# PX4FMUv1_7.net
KiCad netlist of a schematic drawn in EAGLE
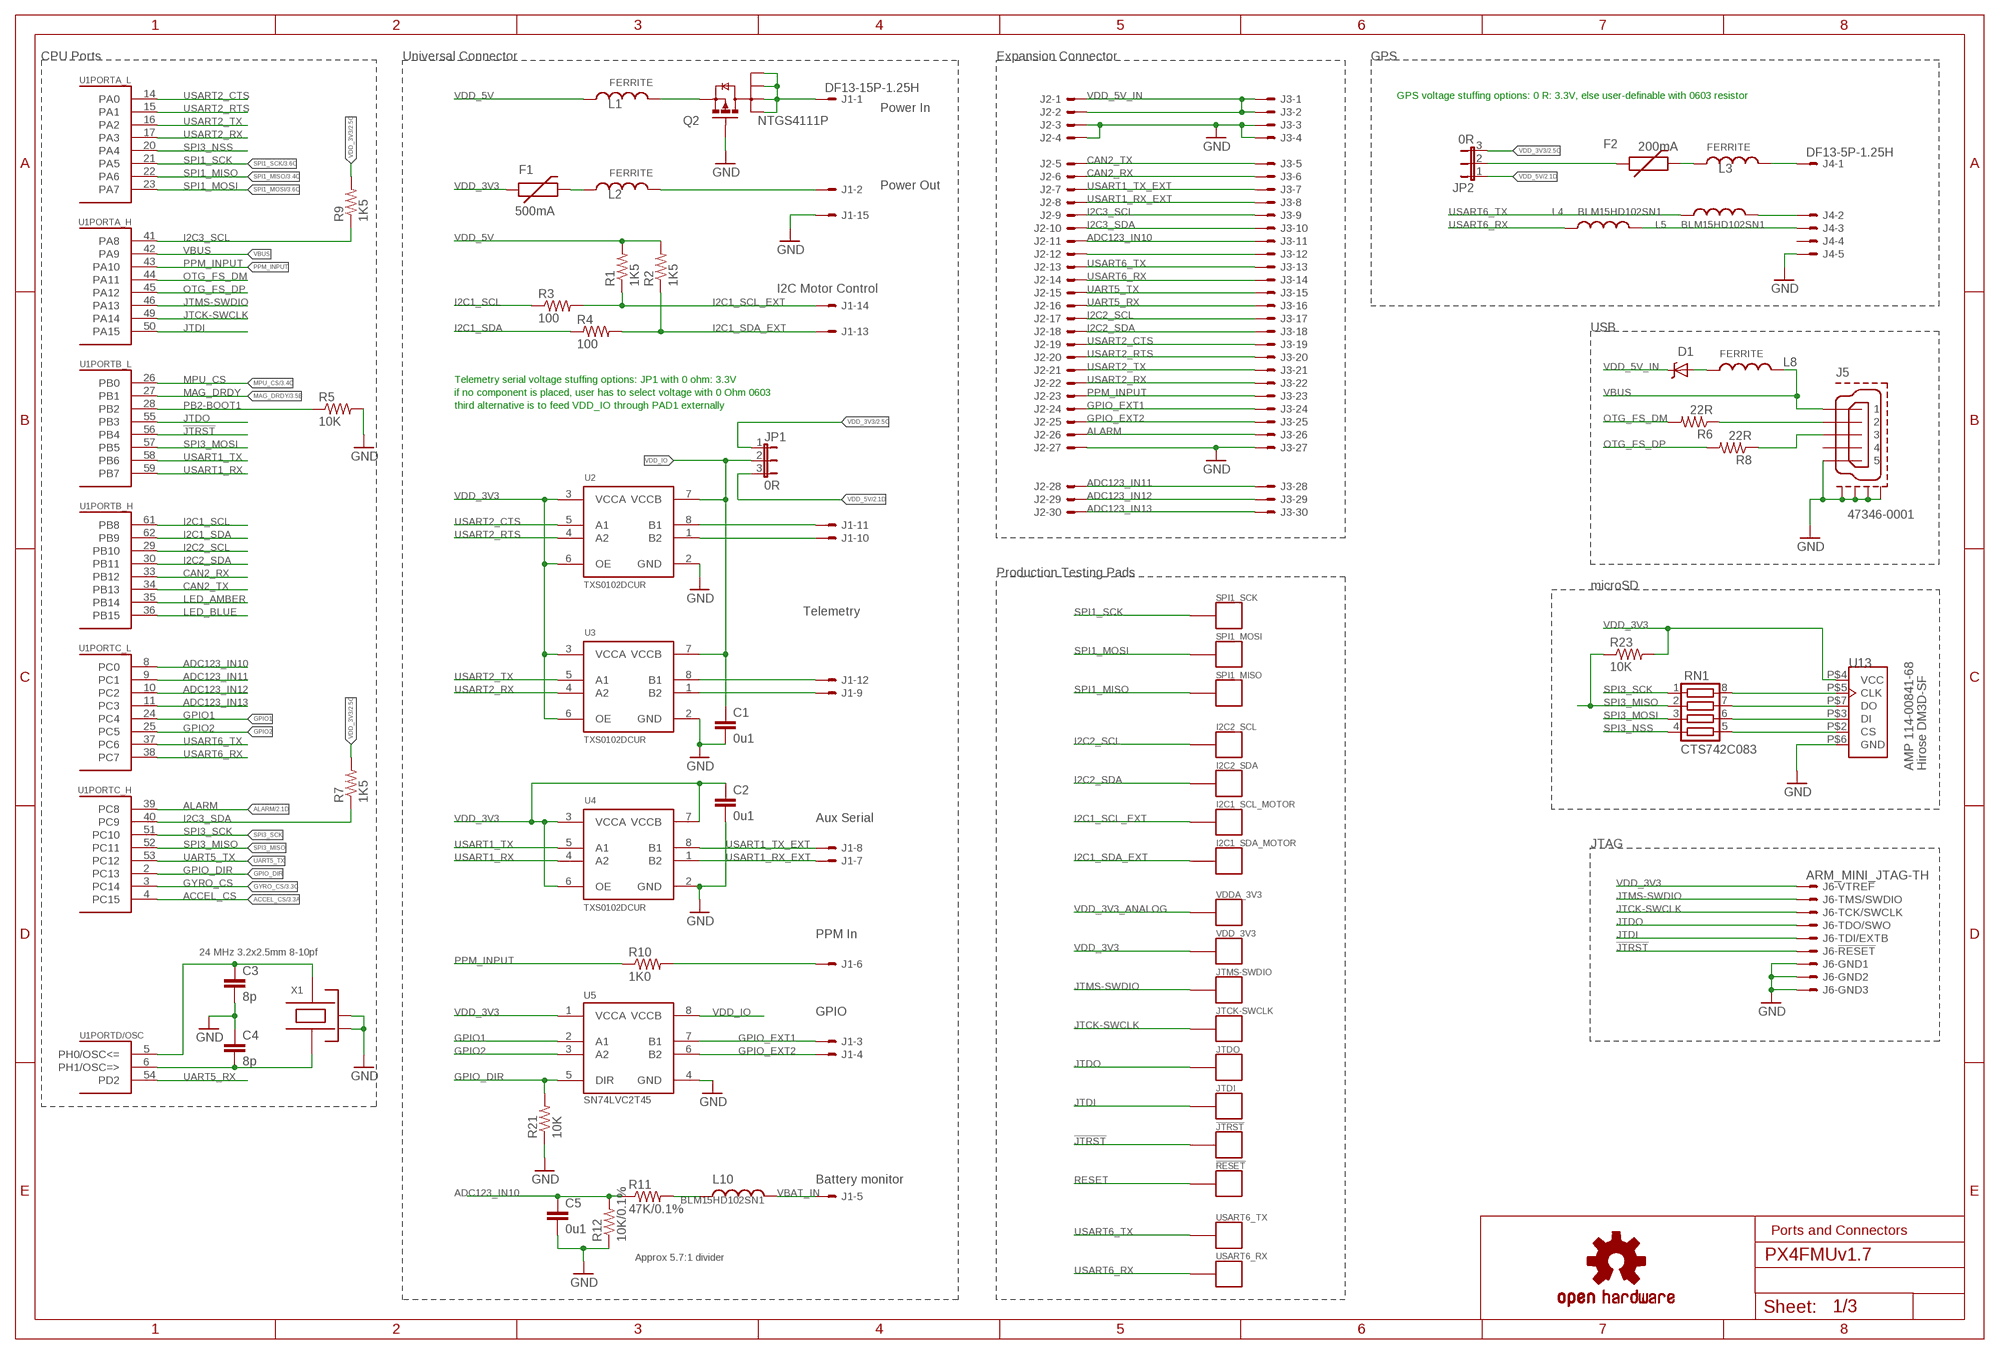
[diagram p0: schematic, sheet 1]
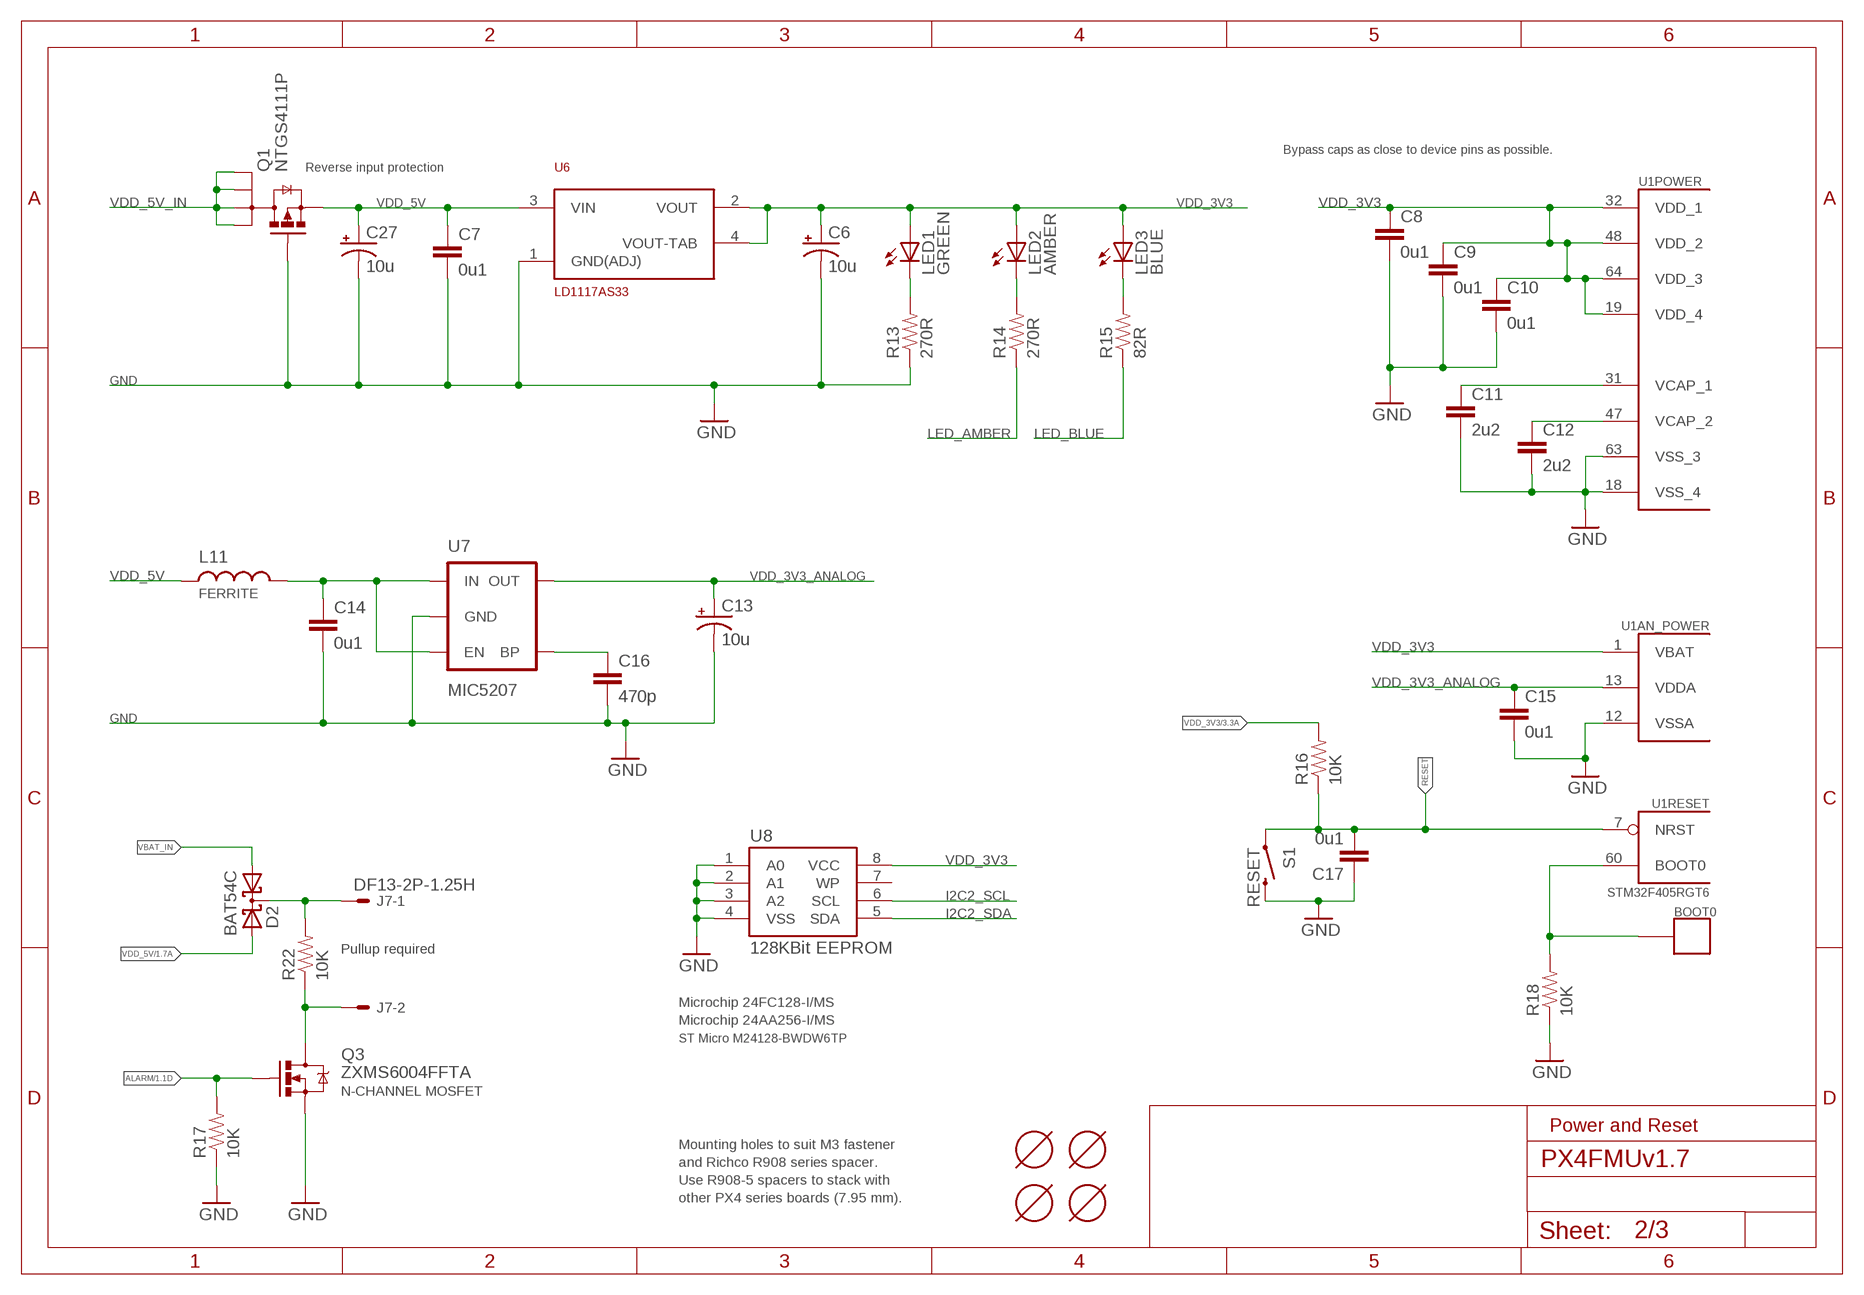
[diagram p1: schematic, sheet 2]
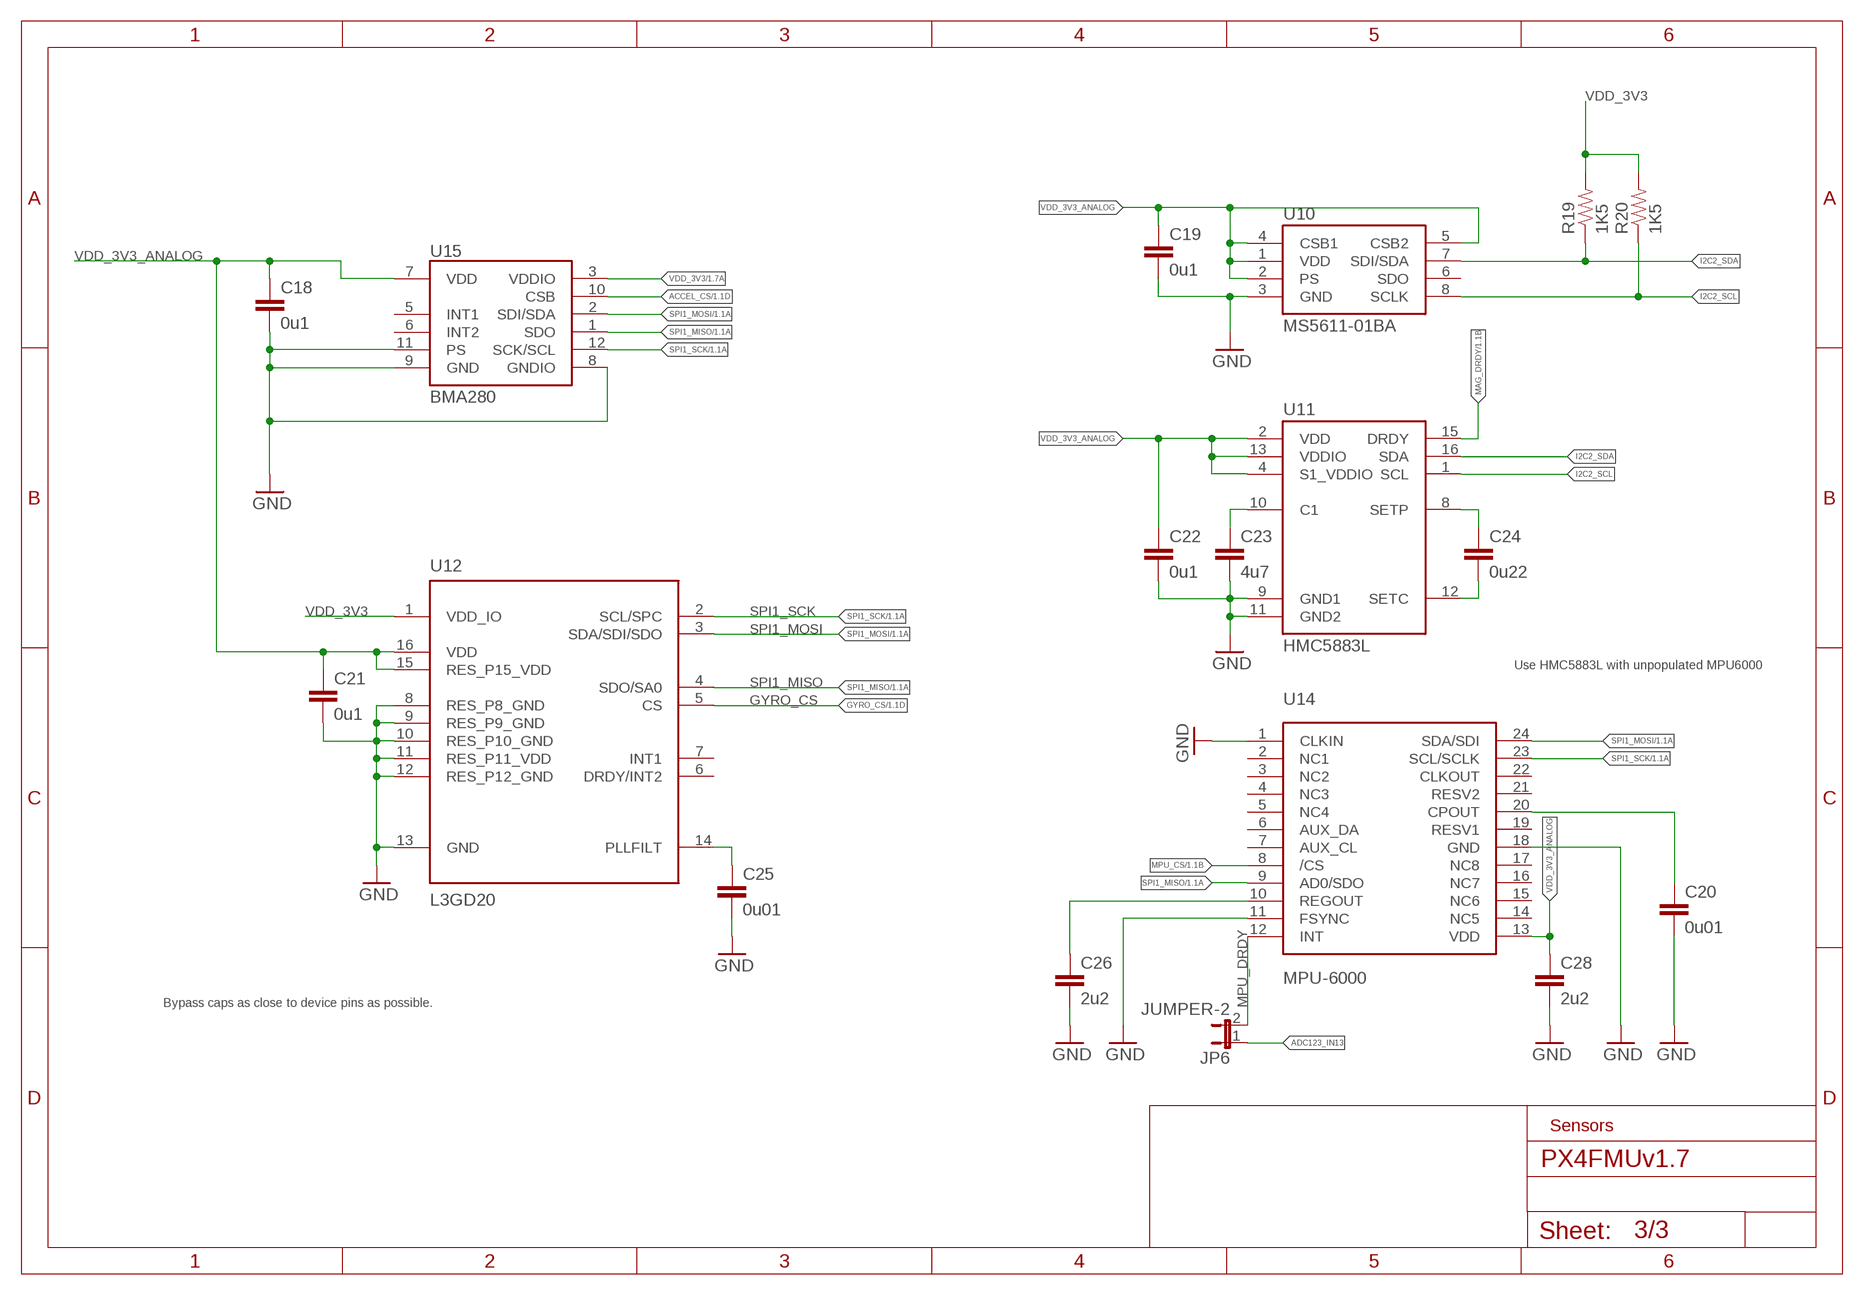
[diagram p2: schematic, sheet 3]

(export (version "E")
  (design (tool "Eeschema 10.0.6"))
  (components
    (comp (ref "BOOT0")
      (value "PAD.04")
      (footprint "eagle-import:PAD.04X.04")
      (libsource (lib "eagle-import") (part "PAD.04"))
    )
    (comp (ref "C6")
      (value "10u")
      (footprint "eagle-import:EIA3216")
      (fields (field (name "PARTNO") "F931A106MAA"))
      (libsource (lib "eagle-import") (part "CAP_POL1206"))
    )
    (comp (ref "C7")
      (value "0u1")
      (footprint "eagle-import:0402-CAP")
      (fields (field (name "PARTNO") "CC0402ZRY5V7BB104"))
      (libsource (lib "eagle-import") (part "CAP0402-CAP"))
    )
    (comp (ref "C8")
      (value "0u1")
      (footprint "eagle-import:0402-CAP")
      (fields (field (name "PARTNO") "CC0402ZRY5V7BB104"))
      (libsource (lib "eagle-import") (part "CAP0402-CAP"))
    )
    (comp (ref "C9")
      (value "0u1")
      (footprint "eagle-import:0402-CAP")
      (fields (field (name "PARTNO") "CC0402ZRY5V7BB104"))
      (libsource (lib "eagle-import") (part "CAP0402-CAP"))
    )
    (comp (ref "C10")
      (value "0u1")
      (footprint "eagle-import:0402-CAP")
      (fields (field (name "PARTNO") "CC0402ZRY5V7BB104"))
      (libsource (lib "eagle-import") (part "CAP0402-CAP"))
    )
    (comp (ref "C11")
      (value "2u2")
      (footprint "eagle-import:0402-CAP")
      (fields (field (name "PARTNO") "C1608Y5V1C225Z"))
      (libsource (lib "eagle-import") (part "CAP0402-CAP"))
    )
    (comp (ref "C12")
      (value "2u2")
      (footprint "eagle-import:0402-CAP")
      (fields (field (name "PARTNO") "C1608Y5V1C225Z"))
      (libsource (lib "eagle-import") (part "CAP0402-CAP"))
    )
    (comp (ref "C13")
      (value "10u")
      (footprint "eagle-import:EIA3216")
      (fields (field (name "PARTNO") "F931A106MAA"))
      (libsource (lib "eagle-import") (part "CAP_POL1206"))
    )
    (comp (ref "C14")
      (value "0u1")
      (footprint "eagle-import:0402-CAP")
      (fields (field (name "PARTNO") "CC0402ZRY5V7BB104"))
      (libsource (lib "eagle-import") (part "CAP0402-CAP"))
    )
    (comp (ref "C15")
      (value "0u1")
      (footprint "eagle-import:0402-CAP")
      (fields (field (name "PARTNO") "CC0402ZRY5V7BB104"))
      (libsource (lib "eagle-import") (part "CAP0402-CAP"))
    )
    (comp (ref "C16")
      (value "470p")
      (footprint "eagle-import:0402-CAP")
      (fields (field (name "PARTNO") "CC0402KRX7R9BB471"))
      (libsource (lib "eagle-import") (part "CAP0402-CAP"))
    )
    (comp (ref "C17")
      (value "0u1")
      (footprint "eagle-import:0402-CAP")
      (fields (field (name "PARTNO") "CC0402ZRY5V7BB104"))
      (libsource (lib "eagle-import") (part "CAP0402-CAP"))
    )
    (comp (ref "C27")
      (value "10u")
      (footprint "eagle-import:EIA3216")
      (fields (field (name "PARTNO") "F931A106MAA"))
      (libsource (lib "eagle-import") (part "CAP_POL1206"))
    )
    (comp (ref "D2")
      (value "BAT54C")
      (footprint "eagle-import:SOT23-3")
      (fields (field (name "PARTNO") "BAT54C-7-F"))
      (libsource (lib "eagle-import") (part "BAT54C"))
    )
    (comp (ref "J7")
      (value "DF13-2P-1.25H")
      (footprint "eagle-import:DF13A-2P-1.25H")
      (fields (field (name "PARTNO") "DF13-2P-1.25H(20)"))
      (libsource (lib "eagle-import") (part "DF13-2P-1.25?H"))
    )
    (comp (ref "L11")
      (value "FERRITE")
      (footprint "eagle-import:0402-IND")
      (fields (field (name "PARTNO") "BKP1005HS121-T"))
      (libsource (lib "eagle-import") (part "INDUCTOR0402"))
    )
    (comp (ref "LED1")
      (value "GREEN")
      (footprint "eagle-import:LED-0603")
      (fields (field (name "PARTNO") "LNJ337W83RA"))
      (libsource (lib "eagle-import") (part "LED0603"))
    )
    (comp (ref "LED2")
      (value "AMBER")
      (footprint "eagle-import:LED-0603")
      (fields (field (name "PARTNO") "LNJ437W84RA"))
      (libsource (lib "eagle-import") (part "LED0603"))
    )
    (comp (ref "LED3")
      (value "BLUE")
      (footprint "eagle-import:LED-0603")
      (fields (field (name "PARTNO") "LNJ937W8CRA"))
      (libsource (lib "eagle-import") (part "LED0603"))
    )
    (comp (ref "Q1")
      (value "NTGS4111P")
      (footprint "eagle-import:TSOP-6")
      (libsource (lib "eagle-import") (part "NTGS4111P"))
    )
    (comp (ref "Q3")
      (value "ZXMS6004FFTA")
      (footprint "eagle-import:SOT23-3")
      (libsource (lib "eagle-import") (part "MOSFET-NCHANNELSMD"))
    )
    (comp (ref "R13")
      (value "270R")
      (footprint "eagle-import:0402-RES")
      (fields (field (name "PARTNO") "RC0402JR-07270RL"))
      (libsource (lib "eagle-import") (part "RESISTOR0402-RES"))
    )
    (comp (ref "R14")
      (value "270R")
      (footprint "eagle-import:0402-RES")
      (fields (field (name "PARTNO") "RC0402JR-07270RL"))
      (libsource (lib "eagle-import") (part "RESISTOR0402-RES"))
    )
    (comp (ref "R15")
      (value "82R")
      (footprint "eagle-import:0402-RES")
      (fields (field (name "PARTNO") "RC0402JR-0782RL"))
      (libsource (lib "eagle-import") (part "RESISTOR0402-RES"))
    )
    (comp (ref "R16")
      (value "10K")
      (footprint "eagle-import:0402-RES")
      (fields (field (name "PARTNO") "RMCF0402FT10K0"))
      (libsource (lib "eagle-import") (part "RESISTOR0402-RES"))
    )
    (comp (ref "R17")
      (value "10K")
      (footprint "eagle-import:0402-RES")
      (fields (field (name "PARTNO") "RMCF0402FT10K0"))
      (libsource (lib "eagle-import") (part "RESISTOR0402-RES"))
    )
    (comp (ref "R18")
      (value "10K")
      (footprint "eagle-import:0402-RES")
      (fields (field (name "PARTNO") "RMCF0402FT10K0"))
      (libsource (lib "eagle-import") (part "RESISTOR0402-RES"))
    )
    (comp (ref "R22")
      (value "10K")
      (footprint "eagle-import:0402-RES")
      (fields (field (name "PARTNO") "RMCF0402FT10K0"))
      (libsource (lib "eagle-import") (part "RESISTOR0402-RES"))
    )
    (comp (ref "S1")
      (value "RESET")
      (footprint "eagle-import:EVQP7J01K")
      (fields (field (name "PARTNO") "EVQP7J01K"))
      (libsource (lib "eagle-import") (part "SWITCH-MOMENTARY-2"))
    )
    (comp (ref "U$1")
      (value "MOUNT-HOLE3.1MM")
      (footprint "eagle-import:MOUNT-HOLE3.1")
      (libsource (lib "eagle-import") (part "MOUNT-HOLE3.1MM"))
    )
    (comp (ref "U$2")
      (value "MOUNT-HOLE3.1MM")
      (footprint "eagle-import:MOUNT-HOLE3.1")
      (libsource (lib "eagle-import") (part "MOUNT-HOLE3.1MM"))
    )
    (comp (ref "U$3")
      (value "MOUNT-HOLE3.1MM")
      (footprint "eagle-import:MOUNT-HOLE3.1")
      (libsource (lib "eagle-import") (part "MOUNT-HOLE3.1MM"))
    )
    (comp (ref "U$4")
      (value "MOUNT-HOLE3.1MM")
      (footprint "eagle-import:MOUNT-HOLE3.1")
      (libsource (lib "eagle-import") (part "MOUNT-HOLE3.1MM"))
    )
    (comp (ref "U1")
      (value "STM32F405RGT6")
      (footprint "eagle-import:TQFP64")
      (fields (field (name "PARTNO") "STM32F405RGT6"))
      (libsource (lib "eagle-import") (part "STM32F20X_TQFP64"))
    )
    (comp (ref "U6")
      (value "LD1117AS33")
      (footprint "eagle-import:SOT-223")
      (libsource (lib "eagle-import") (part "LD1117AS33"))
    )
    (comp (ref "U7")
      (value "MIC5207")
      (footprint "eagle-import:SOT23-5")
      (fields (field (name "PARTNO") "MIC5207-3.3YM5"))
      (libsource (lib "eagle-import") (part "V_REG_LDOSMD"))
    )
    (comp (ref "U8")
      (value "128KBit EEPROM")
      (footprint "eagle-import:MSOP-8")
      (fields (field (name "PARTNO") "24FC128-I/MS"))
      (libsource (lib "eagle-import") (part "EEPROM-I2CMSOP"))
    )
    (comp (ref "!JTRST")
      (value "PAD.04")
      (footprint "eagle-import:PAD.04X.04")
      (libsource (lib "eagle-import") (part "PAD.04"))
    )
    (comp (ref "!RESET")
      (value "PAD.04")
      (footprint "eagle-import:PAD.04X.04")
      (libsource (lib "eagle-import") (part "PAD.04"))
    )
    (comp (ref "C1")
      (value "0u1")
      (footprint "eagle-import:0402-CAP")
      (fields (field (name "PARTNO") "CC0402ZRY5V7BB104"))
      (libsource (lib "eagle-import") (part "CAP0402-CAP"))
    )
    (comp (ref "C2")
      (value "0u1")
      (footprint "eagle-import:0402-CAP")
      (fields (field (name "PARTNO") "CC0402ZRY5V7BB104"))
      (libsource (lib "eagle-import") (part "CAP0402-CAP"))
    )
    (comp (ref "C3")
      (value "8p")
      (footprint "eagle-import:0402-CAP")
      (fields (field (name "PARTNO") "C1005C0G1H080C"))
      (libsource (lib "eagle-import") (part "CAP0402-CAP"))
    )
    (comp (ref "C4")
      (value "8p")
      (footprint "eagle-import:0402-CAP")
      (fields (field (name "PARTNO") "C1005C0G1H080C"))
      (libsource (lib "eagle-import") (part "CAP0402-CAP"))
    )
    (comp (ref "C5")
      (value "0u1")
      (footprint "eagle-import:0402-CAP")
      (fields (field (name "PARTNO") "CC0402ZRY5V7BB104"))
      (libsource (lib "eagle-import") (part "CAP0402-CAP"))
    )
    (comp (ref "D1")
      (value "MSS1P4-M3")
      (footprint "eagle-import:MICROSMP")
      (fields (field (name "PARTNO") "MSS1P4-M3/89A"))
      (libsource (lib "eagle-import") (part "DIODE-SCHOTTKY_MSMP"))
    )
    (comp (ref "F1")
      (value "500mA")
      (footprint "eagle-import:0402-PTC")
      (fields (field (name "PARTNO") "MF-FSMF050X-2"))
      (libsource (lib "eagle-import") (part "PTC0402"))
    )
    (comp (ref "F2")
      (value "200mA")
      (footprint "eagle-import:0402-PTC")
      (fields (field (name "PARTNO") "MF-FSMF020X-2"))
      (libsource (lib "eagle-import") (part "PTC0402"))
    )
    (comp (ref "I2C1_SCL_MOTOR")
      (value "PAD.03")
      (footprint "eagle-import:PAD.03X.03")
      (libsource (lib "eagle-import") (part "PAD.03"))
    )
    (comp (ref "I2C1_SDA_MOTOR")
      (value "PAD.03")
      (footprint "eagle-import:PAD.03X.03")
      (libsource (lib "eagle-import") (part "PAD.03"))
    )
    (comp (ref "I2C2_SCL")
      (value "PAD.03")
      (footprint "eagle-import:PAD.03X.03")
      (libsource (lib "eagle-import") (part "PAD.03"))
    )
    (comp (ref "I2C2_SDA")
      (value "PAD.04")
      (footprint "eagle-import:PAD.04X.04")
      (libsource (lib "eagle-import") (part "PAD.04"))
    )
    (comp (ref "J1")
      (value "DF13-15P-1.25H")
      (footprint "eagle-import:DF13A-15P-1.25H")
      (fields (field (name "PARTNO") "DF13A-15P-1.25H(20)"))
      (libsource (lib "eagle-import") (part "DF13-15P-1.25?H"))
    )
    (comp (ref "J2")
      (value "HEADER_2X15-REV")
      (footprint "eagle-import:HEADER_2MM_2X15_REVERSE")
      (fields (field (name "BOM") "EXCLUDE") (field (name "PARTNO") "953230-2000-AR-PR"))
      (libsource (lib "eagle-import") (part "HEADER_2X15-REV"))
    )
    (comp (ref "J3")
      (value "HEADER_2X15")
      (footprint "eagle-import:HEADER_2MM_2X15")
      (fields (field (name "PARTNO") "953230-2000-AR-PR"))
      (libsource (lib "eagle-import") (part "HEADER_2X15-SMD"))
    )
    (comp (ref "J4")
      (value "DF13-5P-1.25H")
      (footprint "eagle-import:DF13A-5P-1.25H")
      (fields (field (name "PARTNO") "DF13A-5P-1.25H(20)"))
      (libsource (lib "eagle-import") (part "DF13-5P-1.25?H"))
    )
    (comp (ref "J5")
      (value "47346-0001")
      (footprint "eagle-import:MOLEX-47346-0001")
      (libsource (lib "eagle-import") (part "MOLEX-47346-0001"))
    )
    (comp (ref "J6")
      (value "ARM_MINI_JTAG-TH")
      (footprint "eagle-import:FTSH-105-01-XXX-DV")
      (fields (field (name "PARTNO") "M50-3900542"))
      (libsource (lib "eagle-import") (part "ARM_MINI_JTAG-TH"))
    )
    (comp (ref "JP1")
      (value "0R")
      (footprint "eagle-import:SJ_3_0603_PASTE1&2")
      (fields (field (name "PARTNO") "RMCF0402ZT0R00"))
      (libsource (lib "eagle-import") (part "JUMPER-30603"))
    )
    (comp (ref "JP2")
      (value "0R")
      (footprint "eagle-import:SJ_3_0603_PASTE1&2")
      (fields (field (name "PARTNO") "RMCF0402ZT0R00"))
      (libsource (lib "eagle-import") (part "JUMPER-30603"))
    )
    (comp (ref "JTCK-SWCLK")
      (value "PAD.04")
      (footprint "eagle-import:PAD.04X.04")
      (libsource (lib "eagle-import") (part "PAD.04"))
    )
    (comp (ref "JTDI")
      (value "PAD.04")
      (footprint "eagle-import:PAD.04X.04")
      (libsource (lib "eagle-import") (part "PAD.04"))
    )
    (comp (ref "JTDO")
      (value "PAD.04")
      (footprint "eagle-import:PAD.04X.04")
      (libsource (lib "eagle-import") (part "PAD.04"))
    )
    (comp (ref "JTMS-SWDIO")
      (value "PAD.04")
      (footprint "eagle-import:PAD.04X.04")
      (libsource (lib "eagle-import") (part "PAD.04"))
    )
    (comp (ref "L1")
      (value "FERRITE")
      (footprint "eagle-import:0402-IND")
      (fields (field (name "PARTNO") "BKP1005HS121-T"))
      (libsource (lib "eagle-import") (part "INDUCTOR0402"))
    )
    (comp (ref "L2")
      (value "FERRITE")
      (footprint "eagle-import:0402-IND")
      (fields (field (name "PARTNO") "BKP1005HS121-T"))
      (libsource (lib "eagle-import") (part "INDUCTOR0402"))
    )
    (comp (ref "L3")
      (value "FERRITE")
      (footprint "eagle-import:0402-IND")
      (fields (field (name "PARTNO") "BKP1005HS121-T"))
      (libsource (lib "eagle-import") (part "INDUCTOR0402"))
    )
    (comp (ref "L4")
      (value "BLM15HD102SN1")
      (footprint "eagle-import:0402-IND")
      (libsource (lib "eagle-import") (part "INDUCTOR0402"))
    )
    (comp (ref "L5")
      (value "BLM15HD102SN1")
      (footprint "eagle-import:0402-IND")
      (libsource (lib "eagle-import") (part "INDUCTOR0402"))
    )
    (comp (ref "L8")
      (value "FERRITE")
      (footprint "eagle-import:0402-IND")
      (fields (field (name "PARTNO") "BKP1005HS121-T"))
      (libsource (lib "eagle-import") (part "INDUCTOR0402"))
    )
    (comp (ref "L10")
      (value "BLM15HD102SN1")
      (footprint "eagle-import:0402-IND")
      (libsource (lib "eagle-import") (part "INDUCTOR0402"))
    )
    (comp (ref "Q2")
      (value "NTGS4111P")
      (footprint "eagle-import:TSOP-6")
      (libsource (lib "eagle-import") (part "NTGS4111P"))
    )
    (comp (ref "R1")
      (value "1K5")
      (footprint "eagle-import:0402-RES")
      (fields (field (name "PARTNO") "RMCF0402JT1K50"))
      (libsource (lib "eagle-import") (part "RESISTOR0402-RES"))
    )
    (comp (ref "R2")
      (value "1K5")
      (footprint "eagle-import:0402-RES")
      (fields (field (name "PARTNO") "RMCF0402JT1K50"))
      (libsource (lib "eagle-import") (part "RESISTOR0402-RES"))
    )
    (comp (ref "R3")
      (value "100")
      (footprint "eagle-import:0402-RES")
      (fields (field (name "PARTNO") "RMCF0402JT100R"))
      (libsource (lib "eagle-import") (part "RESISTOR0402-RES"))
    )
    (comp (ref "R4")
      (value "100")
      (footprint "eagle-import:0402-RES")
      (fields (field (name "PARTNO") "RMCF0402JT100R"))
      (libsource (lib "eagle-import") (part "RESISTOR0402-RES"))
    )
    (comp (ref "R5")
      (value "10K")
      (footprint "eagle-import:0402-RES")
      (fields (field (name "PARTNO") "RMCF0402FT10K0"))
      (libsource (lib "eagle-import") (part "RESISTOR0402-RES"))
    )
    (comp (ref "R6")
      (value "22R")
      (footprint "eagle-import:0402-RES")
      (fields (field (name "PARTNO") "RMCF0402JT22R0"))
      (libsource (lib "eagle-import") (part "RESISTOR0402-RES"))
    )
    (comp (ref "R7")
      (value "1K5")
      (footprint "eagle-import:0402-RES")
      (fields (field (name "PARTNO") "RMCF0402JT1K50"))
      (libsource (lib "eagle-import") (part "RESISTOR0402-RES"))
    )
    (comp (ref "R8")
      (value "22R")
      (footprint "eagle-import:0402-RES")
      (fields (field (name "PARTNO") "RMCF0402JT22R0"))
      (libsource (lib "eagle-import") (part "RESISTOR0402-RES"))
    )
    (comp (ref "R9")
      (value "1K5")
      (footprint "eagle-import:0402-RES")
      (fields (field (name "PARTNO") "RMCF0402JT1K50"))
      (libsource (lib "eagle-import") (part "RESISTOR0402-RES"))
    )
    (comp (ref "R10")
      (value "1K0")
      (footprint "eagle-import:0402-RES")
      (fields (field (name "PARTNO") "RMCF0402JT1K00"))
      (libsource (lib "eagle-import") (part "RESISTOR0402-RES"))
    )
    (comp (ref "R11")
      (value "47K/0.1%")
      (footprint "eagle-import:0402-RES")
      (fields (field (name "PARTNO") "ERA-2AEB473X"))
      (libsource (lib "eagle-import") (part "RESISTOR0402-RES"))
    )
    (comp (ref "R12")
      (value "10K/0.1%")
      (footprint "eagle-import:0402-RES")
      (fields (field (name "PARTNO") "ERA-2AEB103X"))
      (libsource (lib "eagle-import") (part "RESISTOR0402-RES"))
    )
    (comp (ref "R21")
      (value "10K")
      (footprint "eagle-import:0402-RES")
      (fields (field (name "PARTNO") "RMCF0402FT10K0"))
      (libsource (lib "eagle-import") (part "RESISTOR0402-RES"))
    )
    (comp (ref "R23")
      (value "10K")
      (footprint "eagle-import:0402-RES")
      (fields (field (name "PARTNO") "RMCF0402FT10K0"))
      (libsource (lib "eagle-import") (part "RESISTOR0402-RES"))
    )
    (comp (ref "RN1")
      (value "CTS742C083")
      (footprint "eagle-import:CTS742C083")
      (fields (field (name "PARTNO") "TC164-JR-07100RL"))
      (libsource (lib "eagle-import") (part "CTS742C083"))
    )
    (comp (ref "SPI1_MISO")
      (value "PAD.04")
      (footprint "eagle-import:PAD.04X.04")
      (libsource (lib "eagle-import") (part "PAD.04"))
    )
    (comp (ref "SPI1_MOSI")
      (value "PAD.04")
      (footprint "eagle-import:PAD.04X.04")
      (libsource (lib "eagle-import") (part "PAD.04"))
    )
    (comp (ref "SPI1_SCK")
      (value "PAD.04")
      (footprint "eagle-import:PAD.04X.04")
      (libsource (lib "eagle-import") (part "PAD.04"))
    )
    (comp (ref "U$7")
      (value "OSHW-LOGOS")
      (footprint "eagle-import:OSHW-LOGO-S")
      (libsource (lib "eagle-import") (part "OSHW-LOGOS"))
    )
    (comp (ref "U2")
      (value "TXS0102DCUR")
      (footprint "eagle-import:TI-DCU")
      (libsource (lib "eagle-import") (part "TXS0102DCUR"))
    )
    (comp (ref "U3")
      (value "TXS0102DCUR")
      (footprint "eagle-import:TI-DCU")
      (libsource (lib "eagle-import") (part "TXS0102DCUR"))
    )
    (comp (ref "U4")
      (value "TXS0102DCUR")
      (footprint "eagle-import:TI-DCU")
      (libsource (lib "eagle-import") (part "TXS0102DCUR"))
    )
    (comp (ref "U5")
      (value "SN74LVC2T45")
      (footprint "eagle-import:TI-DCU")
      (libsource (lib "eagle-import") (part "SN74LVC2T45DCUR"))
    )
    (comp (ref "U13")
      (value "AMP 114-00841-68")
      (footprint "eagle-import:AMPHENOL_114-00841-68")
      (fields (field (name "PARTNO") "114-00841-68"))
      (libsource (lib "eagle-import") (part "SF-MICROSDAMP-114-00841-68"))
    )
    (comp (ref "USART6_RX")
      (value "PAD.04")
      (footprint "eagle-import:PAD.04X.04")
      (libsource (lib "eagle-import") (part "PAD.04"))
    )
    (comp (ref "USART6_TX")
      (value "PAD.04")
      (footprint "eagle-import:PAD.04X.04")
      (libsource (lib "eagle-import") (part "PAD.04"))
    )
    (comp (ref "VDDA_3V3")
      (value "PAD.04")
      (footprint "eagle-import:PAD.04X.04")
      (libsource (lib "eagle-import") (part "PAD.04"))
    )
    (comp (ref "VDD_3V3")
      (value "PAD.04")
      (footprint "eagle-import:PAD.04X.04")
      (libsource (lib "eagle-import") (part "PAD.04"))
    )
    (comp (ref "X1")
      (value "24 MHz 3.2x2.5mm 8-10pf")
      (footprint "eagle-import:OSCILLATOR-3.2X2.5")
      (fields (field (name "PARTNO") "NX3225SA-24.000000MHZ"))
      (libsource (lib "eagle-import") (part "OSCILLATOR-3.2X2.5"))
    )
    (comp (ref "C18")
      (value "0u1")
      (footprint "eagle-import:0402-CAP")
      (fields (field (name "PARTNO") "CC0402ZRY5V7BB104"))
      (libsource (lib "eagle-import") (part "CAP0402-CAP"))
    )
    (comp (ref "C19")
      (value "0u1")
      (footprint "eagle-import:0402-CAP")
      (fields (field (name "PARTNO") "CC0402ZRY5V7BB104"))
      (libsource (lib "eagle-import") (part "CAP0402-CAP"))
    )
    (comp (ref "C20")
      (value "0u01")
      (footprint "eagle-import:0402-CAP")
      (fields (field (name "PARTNO") "CC0402KRX7R7BB103"))
      (libsource (lib "eagle-import") (part "CAP0402-CAP"))
    )
    (comp (ref "C21")
      (value "0u1")
      (footprint "eagle-import:0402-CAP")
      (fields (field (name "PARTNO") "CC0402ZRY5V7BB104"))
      (libsource (lib "eagle-import") (part "CAP0402-CAP"))
    )
    (comp (ref "C22")
      (value "0u1")
      (footprint "eagle-import:0402-CAP")
      (fields (field (name "PARTNO") "CC0402ZRY5V7BB104"))
      (libsource (lib "eagle-import") (part "CAP0402-CAP"))
    )
    (comp (ref "C23")
      (value "4u7")
      (footprint "eagle-import:0402-CAP")
      (fields (field (name "PARTNO") "C1608Y5V0J475Z"))
      (libsource (lib "eagle-import") (part "CAP0402-CAP"))
    )
    (comp (ref "C24")
      (value "0u22")
      (footprint "eagle-import:0402-CAP")
      (fields (field (name "PARTNO") "C1005Y5V1C224Z"))
      (libsource (lib "eagle-import") (part "CAP0402-CAP"))
    )
    (comp (ref "C25")
      (value "0u01")
      (footprint "eagle-import:0402-CAP")
      (fields (field (name "PARTNO") "CC0402KRX7R7BB103"))
      (libsource (lib "eagle-import") (part "CAP0402-CAP"))
    )
    (comp (ref "C26")
      (value "2u2")
      (footprint "eagle-import:0402-CAP")
      (fields (field (name "PARTNO") "C1608Y5V1C225Z"))
      (libsource (lib "eagle-import") (part "CAP0402-CAP"))
    )
    (comp (ref "C28")
      (value "2u2")
      (footprint "eagle-import:0402-CAP")
      (fields (field (name "PARTNO") "C1608Y5V1C225Z"))
      (libsource (lib "eagle-import") (part "CAP0402-CAP"))
    )
    (comp (ref "JP6")
      (value "JUMPER-2")
      (footprint "eagle-import:SJ_2")
      (libsource (lib "eagle-import") (part "JUMPER-2"))
    )
    (comp (ref "R19")
      (value "1K5")
      (footprint "eagle-import:0402-RES")
      (fields (field (name "PARTNO") "RMCF0402JT1K50"))
      (libsource (lib "eagle-import") (part "RESISTOR0402-RES"))
    )
    (comp (ref "R20")
      (value "1K5")
      (footprint "eagle-import:0402-RES")
      (fields (field (name "PARTNO") "RMCF0402JT1K50"))
      (libsource (lib "eagle-import") (part "RESISTOR0402-RES"))
    )
    (comp (ref "U10")
      (value "MS5611-01BA")
      (footprint "eagle-import:MS5611-01BA")
      (libsource (lib "eagle-import") (part "MS5611-01BA"))
    )
    (comp (ref "U11")
      (value "HMC5883L")
      (footprint "eagle-import:HMC5883L-MAN")
      (libsource (lib "eagle-import") (part "HMC5883L"))
    )
    (comp (ref "U12")
      (value "L3GD20")
      (footprint "eagle-import:L3G4200DH-MAN")
      (libsource (lib "eagle-import") (part "L3G4200DH-LL"))
    )
    (comp (ref "U14")
      (value "MPU-6000")
      (footprint "eagle-import:QFN-24")
      (libsource (lib "eagle-import") (part "MPU-6000"))
    )
    (comp (ref "U15")
      (value "BMA280")
      (footprint "eagle-import:BMA280")
      (libsource (lib "eagle-import") (part "BMA280"))
    )
  )
  (nets
    (net (code "1") (name "ACCEL_CS") (class "Default")
      (node (ref "U1") (pin "4") (pinfunction "PC15_4") (pintype "bidirectional"))
      (node (ref "U15") (pin "10") (pinfunction "CSB_10") (pintype "bidirectional"))
    )
    (net (code "2") (name "ADC123_IN10") (class "Default")
      (node (ref "C5") (pin "1") (pinfunction "1_1") (pintype "passive"))
      (node (ref "J2") (pin "11") (pinfunction "S_11") (pintype "passive"))
      (node (ref "J3") (pin "11") (pinfunction "S_11") (pintype "passive"))
      (node (ref "R11") (pin "1") (pinfunction "1_1") (pintype "passive"))
      (node (ref "R12") (pin "2") (pinfunction "2_2") (pintype "passive"))
      (node (ref "U1") (pin "8") (pinfunction "PC0_8") (pintype "bidirectional"))
    )
    (net (code "3") (name "ADC123_IN11") (class "Default")
      (node (ref "J2") (pin "28") (pinfunction "S_28") (pintype "passive"))
      (node (ref "J3") (pin "28") (pinfunction "S_28") (pintype "passive"))
      (node (ref "U1") (pin "9") (pinfunction "PC1_9") (pintype "bidirectional"))
    )
    (net (code "4") (name "ADC123_IN12") (class "Default")
      (node (ref "J2") (pin "29") (pinfunction "S_29") (pintype "passive"))
      (node (ref "J3") (pin "29") (pinfunction "S_29") (pintype "passive"))
      (node (ref "U1") (pin "10") (pinfunction "PC2_10") (pintype "bidirectional"))
    )
    (net (code "5") (name "ADC123_IN13") (class "Default")
      (node (ref "J2") (pin "30") (pinfunction "S_30") (pintype "passive"))
      (node (ref "J3") (pin "30") (pinfunction "S_30") (pintype "passive"))
      (node (ref "JP6") (pin "1") (pinfunction "1_1") (pintype "passive"))
      (node (ref "U1") (pin "11") (pinfunction "PC3_11") (pintype "bidirectional"))
    )
    (net (code "6") (name "ALARM") (class "Default")
      (node (ref "J2") (pin "26") (pinfunction "S_26") (pintype "passive"))
      (node (ref "J3") (pin "26") (pinfunction "S_26") (pintype "passive"))
      (node (ref "Q3") (pin "1") (pinfunction "G_1") (pintype "passive"))
      (node (ref "R17") (pin "2") (pinfunction "2_2") (pintype "passive"))
      (node (ref "U1") (pin "39") (pinfunction "PC8_39") (pintype "bidirectional"))
    )
    (net (code "7") (name "CAN2_RX") (class "Default")
      (node (ref "J2") (pin "6") (pinfunction "S_6") (pintype "passive"))
      (node (ref "J3") (pin "6") (pinfunction "S_6") (pintype "passive"))
      (node (ref "U1") (pin "33") (pinfunction "PB12_33") (pintype "bidirectional"))
    )
    (net (code "8") (name "CAN2_TX") (class "Default")
      (node (ref "J2") (pin "5") (pinfunction "S_5") (pintype "passive"))
      (node (ref "J3") (pin "5") (pinfunction "S_5") (pintype "passive"))
      (node (ref "U1") (pin "34") (pinfunction "PB13_34") (pintype "bidirectional"))
    )
    (net (code "9") (name "GND") (class "Default")
      (node (ref "C1") (pin "2") (pinfunction "2_2") (pintype "passive"))
      (node (ref "C10") (pin "2") (pinfunction "2_2") (pintype "passive"))
      (node (ref "C11") (pin "2") (pinfunction "2_2") (pintype "passive"))
      (node (ref "C12") (pin "2") (pinfunction "2_2") (pintype "passive"))
      (node (ref "C13") (pin "C") (pinfunction "-_C") (pintype "passive"))
      (node (ref "C14") (pin "2") (pinfunction "2_2") (pintype "passive"))
      (node (ref "C15") (pin "2") (pinfunction "2_2") (pintype "passive"))
      (node (ref "C16") (pin "2") (pinfunction "2_2") (pintype "passive"))
      (node (ref "C17") (pin "1") (pinfunction "1_1") (pintype "passive"))
      (node (ref "C18") (pin "2") (pinfunction "2_2") (pintype "passive"))
      (node (ref "C19") (pin "2") (pinfunction "2_2") (pintype "passive"))
      (node (ref "C2") (pin "2") (pinfunction "2_2") (pintype "passive"))
      (node (ref "C20") (pin "2") (pinfunction "2_2") (pintype "passive"))
      (node (ref "C21") (pin "2") (pinfunction "2_2") (pintype "passive"))
      (node (ref "C22") (pin "2") (pinfunction "2_2") (pintype "passive"))
      (node (ref "C23") (pin "2") (pinfunction "2_2") (pintype "passive"))
      (node (ref "C25") (pin "2") (pinfunction "2_2") (pintype "passive"))
      (node (ref "C26") (pin "2") (pinfunction "2_2") (pintype "passive"))
      (node (ref "C27") (pin "C") (pinfunction "-_C") (pintype "passive"))
      (node (ref "C28") (pin "2") (pinfunction "2_2") (pintype "passive"))
      (node (ref "C3") (pin "2") (pinfunction "2_2") (pintype "passive"))
      (node (ref "C4") (pin "1") (pinfunction "1_1") (pintype "passive"))
      (node (ref "C5") (pin "2") (pinfunction "2_2") (pintype "passive"))
      (node (ref "C6") (pin "C") (pinfunction "-_C") (pintype "passive"))
      (node (ref "C7") (pin "2") (pinfunction "2_2") (pintype "passive"))
      (node (ref "C8") (pin "2") (pinfunction "2_2") (pintype "passive"))
      (node (ref "C9") (pin "2") (pinfunction "2_2") (pintype "passive"))
      (node (ref "J1") (pin "15") (pinfunction "S_15") (pintype "passive"))
      (node (ref "J2") (pin "27") (pinfunction "S_27") (pintype "passive"))
      (node (ref "J2") (pin "3") (pinfunction "S_3") (pintype "passive"))
      (node (ref "J2") (pin "4") (pinfunction "S_4") (pintype "passive"))
      (node (ref "J3") (pin "27") (pinfunction "S_27") (pintype "passive"))
      (node (ref "J3") (pin "3") (pinfunction "S_3") (pintype "passive"))
      (node (ref "J3") (pin "4") (pinfunction "S_4") (pintype "passive"))
      (node (ref "J4") (pin "5") (pinfunction "S_5") (pintype "passive"))
      (node (ref "J5") (pin "GND") (pinfunction "5_GND") (pintype "power_in"))
      (node (ref "J5") (pin "GND1") (pinfunction "GND1_GND1") (pintype "bidirectional"))
      (node (ref "J5") (pin "GND2") (pinfunction "GND2_GND2") (pintype "bidirectional"))
      (node (ref "J5") (pin "GND3") (pinfunction "GND3_GND3") (pintype "bidirectional"))
      (node (ref "J5") (pin "GND4") (pinfunction "GND4_GND4") (pintype "bidirectional"))
      (node (ref "J6") (pin "3") (pinfunction "S_3") (pintype "passive"))
      (node (ref "J6") (pin "5") (pinfunction "S_5") (pintype "passive"))
      (node (ref "J6") (pin "9") (pinfunction "S_9") (pintype "passive"))
      (node (ref "Q1") (pin "3") (pinfunction "G_3") (pintype "passive"))
      (node (ref "Q2") (pin "3") (pinfunction "G_3") (pintype "passive"))
      (node (ref "Q3") (pin "2") (pinfunction "S_2") (pintype "passive"))
      (node (ref "R12") (pin "1") (pinfunction "1_1") (pintype "passive"))
      (node (ref "R13") (pin "1") (pinfunction "1_1") (pintype "passive"))
      (node (ref "R17") (pin "1") (pinfunction "1_1") (pintype "passive"))
      (node (ref "R18") (pin "1") (pinfunction "1_1") (pintype "passive"))
      (node (ref "R21") (pin "1") (pinfunction "1_1") (pintype "passive"))
      (node (ref "R5") (pin "2") (pinfunction "2_2") (pintype "passive"))
      (node (ref "S1") (pin "B3") (pinfunction "2_B3") (pintype "passive"))
      (node (ref "U1") (pin "12") (pinfunction "VSSA_12") (pintype "power_in"))
      (node (ref "U1") (pin "18") (pinfunction "VSS_4_18") (pintype "power_in"))
      (node (ref "U1") (pin "63") (pinfunction "VSS_3_63") (pintype "power_in"))
      (node (ref "U10") (pin "3") (pinfunction "GND_3") (pintype "bidirectional"))
      (node (ref "U11") (pin "11") (pinfunction "GND2_11") (pintype "bidirectional"))
      (node (ref "U11") (pin "9") (pinfunction "GND1_9") (pintype "bidirectional"))
      (node (ref "U12") (pin "10") (pinfunction "RES_P10_GND_10") (pintype "bidirectional"))
      (node (ref "U12") (pin "11") (pinfunction "RES_P11_VDD_11") (pintype "bidirectional"))
      (node (ref "U12") (pin "12") (pinfunction "RES_P12_GND_12") (pintype "bidirectional"))
      (node (ref "U12") (pin "13") (pinfunction "GND_13") (pintype "bidirectional"))
      (node (ref "U12") (pin "8") (pinfunction "RES_P8_GND_8") (pintype "bidirectional"))
      (node (ref "U12") (pin "9") (pinfunction "RES_P9_GND_9") (pintype "bidirectional"))
      (node (ref "U13") (pin "P$6") (pinfunction "GND_P$6") (pintype "power_in"))
      (node (ref "U14") (pin "1") (pinfunction "CLKIN_1") (pintype "bidirectional"))
      (node (ref "U14") (pin "11") (pinfunction "FSYNC_11") (pintype "bidirectional"))
      (node (ref "U14") (pin "18") (pinfunction "GND_18") (pintype "bidirectional"))
      (node (ref "U15") (pin "11") (pinfunction "PS_11") (pintype "bidirectional"))
      (node (ref "U15") (pin "8") (pinfunction "GNDIO_8") (pintype "bidirectional"))
      (node (ref "U15") (pin "9") (pinfunction "GND_9") (pintype "bidirectional"))
      (node (ref "U2") (pin "2") (pinfunction "GND_2") (pintype "power_in"))
      (node (ref "U3") (pin "2") (pinfunction "GND_2") (pintype "power_in"))
      (node (ref "U4") (pin "2") (pinfunction "GND_2") (pintype "power_in"))
      (node (ref "U5") (pin "4") (pinfunction "GND_4") (pintype "power_in"))
      (node (ref "U6") (pin "1") (pinfunction "GND(ADJ)_1") (pintype "bidirectional"))
      (node (ref "U7") (pin "2") (pinfunction "GND_2") (pintype "input"))
      (node (ref "U8") (pin "1") (pinfunction "A0_1") (pintype "bidirectional"))
      (node (ref "U8") (pin "2") (pinfunction "A1_2") (pintype "bidirectional"))
      (node (ref "U8") (pin "3") (pinfunction "A2_3") (pintype "bidirectional"))
      (node (ref "U8") (pin "4") (pinfunction "VSS_4") (pintype "power_in"))
      (node (ref "X1") (pin "2") (pinfunction "NC_2_2") (pintype "power_in"))
      (node (ref "X1") (pin "4") (pinfunction "NC_4_4") (pintype "power_in"))
    )
    (net (code "10") (name "GPIO1") (class "Default")
      (node (ref "U1") (pin "24") (pinfunction "PC4_24") (pintype "bidirectional"))
      (node (ref "U5") (pin "2") (pinfunction "A1_2") (pintype "bidirectional"))
    )
    (net (code "11") (name "GPIO2") (class "Default")
      (node (ref "U1") (pin "25") (pinfunction "PC5_25") (pintype "bidirectional"))
      (node (ref "U5") (pin "3") (pinfunction "A2_3") (pintype "bidirectional"))
    )
    (net (code "12") (name "GPIO_DIR") (class "Default")
      (node (ref "R21") (pin "2") (pinfunction "2_2") (pintype "passive"))
      (node (ref "U1") (pin "2") (pinfunction "PC13_2") (pintype "bidirectional"))
      (node (ref "U5") (pin "5") (pinfunction "DIR_5") (pintype "input"))
    )
    (net (code "13") (name "GPIO_EXT1") (class "Default")
      (node (ref "J1") (pin "3") (pinfunction "S_3") (pintype "passive"))
      (node (ref "J2") (pin "24") (pinfunction "S_24") (pintype "passive"))
      (node (ref "J3") (pin "24") (pinfunction "S_24") (pintype "passive"))
      (node (ref "U5") (pin "7") (pinfunction "B1_7") (pintype "bidirectional"))
    )
    (net (code "14") (name "GPIO_EXT2") (class "Default")
      (node (ref "J1") (pin "4") (pinfunction "S_4") (pintype "passive"))
      (node (ref "J2") (pin "25") (pinfunction "S_25") (pintype "passive"))
      (node (ref "J3") (pin "25") (pinfunction "S_25") (pintype "passive"))
      (node (ref "U5") (pin "6") (pinfunction "B2_6") (pintype "bidirectional"))
    )
    (net (code "15") (name "GYRO_CS") (class "Default")
      (node (ref "U1") (pin "3") (pinfunction "PC14_3") (pintype "bidirectional"))
      (node (ref "U12") (pin "5") (pinfunction "CS_5") (pintype "input"))
    )
    (net (code "16") (name "I2C1_SCL") (class "Default")
      (node (ref "R3") (pin "1") (pinfunction "1_1") (pintype "passive"))
      (node (ref "U1") (pin "61") (pinfunction "PB8_61") (pintype "bidirectional"))
    )
    (net (code "17") (name "I2C1_SCL_EXT") (class "Default")
      (node (ref "I2C1_SCL_MOTOR") (pin "P$1") (pinfunction "P$1_P$1") (pintype "passive"))
      (node (ref "J1") (pin "14") (pinfunction "S_14") (pintype "passive"))
      (node (ref "R1") (pin "1") (pinfunction "1_1") (pintype "passive"))
      (node (ref "R3") (pin "2") (pinfunction "2_2") (pintype "passive"))
    )
    (net (code "18") (name "I2C1_SDA") (class "Default")
      (node (ref "R4") (pin "1") (pinfunction "1_1") (pintype "passive"))
      (node (ref "U1") (pin "62") (pinfunction "PB9_62") (pintype "bidirectional"))
    )
    (net (code "19") (name "I2C1_SDA_EXT") (class "Default")
      (node (ref "I2C1_SDA_MOTOR") (pin "P$1") (pinfunction "P$1_P$1") (pintype "passive"))
      (node (ref "J1") (pin "13") (pinfunction "S_13") (pintype "passive"))
      (node (ref "R2") (pin "1") (pinfunction "1_1") (pintype "passive"))
      (node (ref "R4") (pin "2") (pinfunction "2_2") (pintype "passive"))
    )
    (net (code "20") (name "I2C2_SCL") (class "Default")
      (node (ref "I2C2_SCL") (pin "P$1") (pinfunction "P$1_P$1") (pintype "passive"))
      (node (ref "J2") (pin "17") (pinfunction "S_17") (pintype "passive"))
      (node (ref "J3") (pin "17") (pinfunction "S_17") (pintype "passive"))
      (node (ref "R20") (pin "1") (pinfunction "1_1") (pintype "passive"))
      (node (ref "U1") (pin "29") (pinfunction "PB10_29") (pintype "bidirectional"))
      (node (ref "U10") (pin "8") (pinfunction "SCLK_8") (pintype "bidirectional"))
      (node (ref "U11") (pin "1") (pinfunction "SCL_1") (pintype "bidirectional"))
      (node (ref "U8") (pin "6") (pinfunction "SCL_6") (pintype "bidirectional"))
    )
    (net (code "21") (name "I2C2_SDA") (class "Default")
      (node (ref "I2C2_SDA") (pin "P$1") (pinfunction "P$1_P$1") (pintype "passive"))
      (node (ref "J2") (pin "18") (pinfunction "S_18") (pintype "passive"))
      (node (ref "J3") (pin "18") (pinfunction "S_18") (pintype "passive"))
      (node (ref "R19") (pin "1") (pinfunction "1_1") (pintype "passive"))
      (node (ref "U1") (pin "30") (pinfunction "PB11_30") (pintype "bidirectional"))
      (node (ref "U10") (pin "7") (pinfunction "SDI/SDA_7") (pintype "bidirectional"))
      (node (ref "U11") (pin "16") (pinfunction "SDA_16") (pintype "bidirectional"))
      (node (ref "U8") (pin "5") (pinfunction "SDA_5") (pintype "bidirectional"))
    )
    (net (code "22") (name "I2C3_SCL") (class "Default")
      (node (ref "J2") (pin "9") (pinfunction "S_9") (pintype "passive"))
      (node (ref "J3") (pin "9") (pinfunction "S_9") (pintype "passive"))
      (node (ref "R9") (pin "1") (pinfunction "1_1") (pintype "passive"))
      (node (ref "U1") (pin "41") (pinfunction "PA8_41") (pintype "bidirectional"))
    )
    (net (code "23") (name "I2C3_SDA") (class "Default")
      (node (ref "J2") (pin "10") (pinfunction "S_10") (pintype "passive"))
      (node (ref "J3") (pin "10") (pinfunction "S_10") (pintype "passive"))
      (node (ref "R7") (pin "1") (pinfunction "1_1") (pintype "passive"))
      (node (ref "U1") (pin "40") (pinfunction "PC9_40") (pintype "bidirectional"))
    )
    (net (code "24") (name "JTCK-SWCLK") (class "Default")
      (node (ref "J6") (pin "4") (pinfunction "S_4") (pintype "passive"))
      (node (ref "JTCK-SWCLK") (pin "P$1") (pinfunction "P$1_P$1") (pintype "passive"))
      (node (ref "U1") (pin "49") (pinfunction "PA14_49") (pintype "bidirectional"))
    )
    (net (code "25") (name "JTDI") (class "Default")
      (node (ref "J6") (pin "8") (pinfunction "S_8") (pintype "passive"))
      (node (ref "JTDI") (pin "P$1") (pinfunction "P$1_P$1") (pintype "passive"))
      (node (ref "U1") (pin "50") (pinfunction "PA15_50") (pintype "bidirectional"))
    )
    (net (code "26") (name "JTDO") (class "Default")
      (node (ref "J6") (pin "6") (pinfunction "S_6") (pintype "passive"))
      (node (ref "JTDO") (pin "P$1") (pinfunction "P$1_P$1") (pintype "passive"))
      (node (ref "U1") (pin "55") (pinfunction "PB3_55") (pintype "bidirectional"))
    )
    (net (code "27") (name "JTMS-SWDIO") (class "Default")
      (node (ref "J6") (pin "2") (pinfunction "S_2") (pintype "passive"))
      (node (ref "JTMS-SWDIO") (pin "P$1") (pinfunction "P$1_P$1") (pintype "passive"))
      (node (ref "U1") (pin "46") (pinfunction "PA13_46") (pintype "bidirectional"))
    )
    (net (code "28") (name "LED_AMBER") (class "Default")
      (node (ref "R14") (pin "1") (pinfunction "1_1") (pintype "passive"))
      (node (ref "U1") (pin "35") (pinfunction "PB14_35") (pintype "bidirectional"))
    )
    (net (code "29") (name "LED_BLUE") (class "Default")
      (node (ref "R15") (pin "1") (pinfunction "1_1") (pintype "passive"))
      (node (ref "U1") (pin "36") (pinfunction "PB15_36") (pintype "bidirectional"))
    )
    (net (code "30") (name "MAG_DRDY") (class "Default")
      (node (ref "U1") (pin "27") (pinfunction "PB1_27") (pintype "bidirectional"))
      (node (ref "U11") (pin "15") (pinfunction "DRDY_15") (pintype "bidirectional"))
    )
    (net (code "31") (name "MPU_CS") (class "Default")
      (node (ref "U1") (pin "26") (pinfunction "PB0_26") (pintype "bidirectional"))
      (node (ref "U14") (pin "8") (pinfunction "/CS_8") (pintype "bidirectional"))
    )
    (net (code "32") (name "Net-(D1-A)") (class "Default")
      (node (ref "D1") (pin "ANODE") (pinfunction "A_ANODE") (pintype "passive"))
      (node (ref "L8") (pin "1") (pinfunction "1_1") (pintype "passive"))
    )
    (net (code "33") (name "Net-(D2-CC)") (class "Default")
      (node (ref "D2") (pin "3") (pinfunction "CC_3") (pintype "passive"))
      (node (ref "J7") (pin "1") (pinfunction "S_1") (pintype "passive"))
      (node (ref "R22") (pin "2") (pinfunction "2_2") (pintype "passive"))
    )
    (net (code "34") (name "Net-(F1-Pad2)") (class "Default")
      (node (ref "F1") (pin "2") (pinfunction "2_2") (pintype "bidirectional"))
      (node (ref "L2") (pin "1") (pinfunction "1_1") (pintype "passive"))
    )
    (net (code "35") (name "Net-(F2-Pad1)") (class "Default")
      (node (ref "F2") (pin "1") (pinfunction "1_1") (pintype "bidirectional"))
      (node (ref "JP2") (pin "2") (pinfunction "2_2") (pintype "passive"))
    )
    (net (code "36") (name "Net-(F2-Pad2)") (class "Default")
      (node (ref "F2") (pin "2") (pinfunction "2_2") (pintype "bidirectional"))
      (node (ref "L3") (pin "1") (pinfunction "1_1") (pintype "passive"))
    )
    (net (code "37") (name "Net-(J1A-S)") (class "Default")
      (node (ref "J1") (pin "1") (pinfunction "S_1") (pintype "passive"))
      (node (ref "Q2") (pin "1") (pinfunction "D_1") (pintype "passive"))
      (node (ref "Q2") (pin "2") (pinfunction "D1_2") (pintype "passive"))
      (node (ref "Q2") (pin "5") (pinfunction "D2_5") (pintype "passive"))
      (node (ref "Q2") (pin "6") (pinfunction "D3_6") (pintype "passive"))
    )
    (net (code "38") (name "Net-(J1B-S)") (class "Default")
      (node (ref "J1") (pin "10") (pinfunction "S_10") (pintype "passive"))
      (node (ref "U2") (pin "1") (pinfunction "B2_1") (pintype "bidirectional"))
    )
    (net (code "39") (name "Net-(J1C-S)") (class "Default")
      (node (ref "J1") (pin "11") (pinfunction "S_11") (pintype "passive"))
      (node (ref "U2") (pin "8") (pinfunction "B1_8") (pintype "bidirectional"))
    )
    (net (code "40") (name "Net-(J1D-S)") (class "Default")
      (node (ref "J1") (pin "12") (pinfunction "S_12") (pintype "passive"))
      (node (ref "U3") (pin "8") (pinfunction "B1_8") (pintype "bidirectional"))
    )
    (net (code "41") (name "Net-(J1H-S)") (class "Default")
      (node (ref "J1") (pin "2") (pinfunction "S_2") (pintype "passive"))
      (node (ref "L2") (pin "2") (pinfunction "2_2") (pintype "passive"))
    )
    (net (code "42") (name "Net-(J1L-S)") (class "Default")
      (node (ref "J1") (pin "6") (pinfunction "S_6") (pintype "passive"))
      (node (ref "R10") (pin "2") (pinfunction "2_2") (pintype "passive"))
    )
    (net (code "43") (name "Net-(J1O-S)") (class "Default")
      (node (ref "J1") (pin "9") (pinfunction "S_9") (pintype "passive"))
      (node (ref "U3") (pin "1") (pinfunction "B2_1") (pintype "bidirectional"))
    )
    (net (code "44") (name "Net-(J2D-S)") (class "Default")
      (node (ref "J2") (pin "12") (pinfunction "S_12") (pintype "passive"))
      (node (ref "J3") (pin "12") (pinfunction "S_12") (pintype "passive"))
    )
    (net (code "45") (name "Net-(J4A-S)") (class "Default")
      (node (ref "J4") (pin "1") (pinfunction "S_1") (pintype "passive"))
      (node (ref "L3") (pin "2") (pinfunction "2_2") (pintype "passive"))
    )
    (net (code "46") (name "Net-(J4B-S)") (class "Default")
      (node (ref "J4") (pin "2") (pinfunction "S_2") (pintype "passive"))
      (node (ref "L5") (pin "2") (pinfunction "2_2") (pintype "passive"))
    )
    (net (code "47") (name "Net-(J4C-S)") (class "Default")
      (node (ref "J4") (pin "3") (pinfunction "S_3") (pintype "passive"))
      (node (ref "L4") (pin "2") (pinfunction "2_2") (pintype "passive"))
    )
    (net (code "48") (name "Net-(J5-2)") (class "Default")
      (node (ref "J5") (pin "D-") (pinfunction "2_D-") (pintype "bidirectional"))
      (node (ref "R6") (pin "1") (pinfunction "1_1") (pintype "passive"))
    )
    (net (code "49") (name "Net-(J5-3)") (class "Default")
      (node (ref "J5") (pin "D+") (pinfunction "3_D+") (pintype "bidirectional"))
      (node (ref "R8") (pin "1") (pinfunction "1_1") (pintype "passive"))
    )
    (net (code "50") (name "Net-(J7B-S)") (class "Default")
      (node (ref "J7") (pin "2") (pinfunction "S_2") (pintype "passive"))
      (node (ref "Q3") (pin "3") (pinfunction "D_3") (pintype "passive"))
      (node (ref "R22") (pin "1") (pinfunction "1_1") (pintype "passive"))
    )
    (net (code "51") (name "Net-(L10-Pad1)") (class "Default")
      (node (ref "L10") (pin "1") (pinfunction "1_1") (pintype "passive"))
      (node (ref "R11") (pin "2") (pinfunction "2_2") (pintype "passive"))
    )
    (net (code "52") (name "Net-(LED1-PadC)") (class "Default")
      (node (ref "LED1") (pin "C") (pinfunction "C_C") (pintype "passive"))
      (node (ref "R13") (pin "2") (pinfunction "2_2") (pintype "passive"))
    )
    (net (code "53") (name "Net-(LED2-PadC)") (class "Default")
      (node (ref "LED2") (pin "C") (pinfunction "C_C") (pintype "passive"))
      (node (ref "R14") (pin "2") (pinfunction "2_2") (pintype "passive"))
    )
    (net (code "54") (name "Net-(LED3-PadC)") (class "Default")
      (node (ref "LED3") (pin "C") (pinfunction "C_C") (pintype "passive"))
      (node (ref "R15") (pin "2") (pinfunction "2_2") (pintype "passive"))
    )
    (net (code "55") (name "Net-(Q2-S)") (class "Default")
      (node (ref "L1") (pin "2") (pinfunction "2_2") (pintype "passive"))
      (node (ref "Q2") (pin "4") (pinfunction "S_4") (pintype "passive"))
    )
    (net (code "56") (name "Net-(U1H-PH0{slash}OSC<=)") (class "Default")
      (node (ref "C3") (pin "1") (pinfunction "1_1") (pintype "passive"))
      (node (ref "U1") (pin "5") (pinfunction "PH0/OSC<=_5") (pintype "bidirectional"))
      (node (ref "X1") (pin "3") (pinfunction "3_3") (pintype "bidirectional"))
    )
    (net (code "57") (name "Net-(U1H-PH1{slash}OSC=>)") (class "Default")
      (node (ref "C4") (pin "2") (pinfunction "2_2") (pintype "passive"))
      (node (ref "U1") (pin "6") (pinfunction "PH1/OSC=>_6") (pintype "bidirectional"))
      (node (ref "X1") (pin "1") (pinfunction "1_1") (pintype "bidirectional"))
    )
    (net (code "58") (name "Net-(U1I-VCAP_1)") (class "Default")
      (node (ref "C11") (pin "1") (pinfunction "1_1") (pintype "passive"))
      (node (ref "U1") (pin "31") (pinfunction "VCAP_1_31") (pintype "power_in"))
    )
    (net (code "59") (name "Net-(U1I-VCAP_2)") (class "Default")
      (node (ref "C12") (pin "1") (pinfunction "1_1") (pintype "passive"))
      (node (ref "U1") (pin "47") (pinfunction "VCAP_2_47") (pintype "power_in"))
    )
    (net (code "60") (name "Net-(U1J-BOOT0)") (class "Default")
      (node (ref "BOOT0") (pin "P$1") (pinfunction "P$1_P$1") (pintype "passive"))
      (node (ref "R18") (pin "2") (pinfunction "2_2") (pintype "passive"))
      (node (ref "U1") (pin "60") (pinfunction "BOOT0_60") (pintype "input"))
    )
    (net (code "61") (name "Net-(U7-BP)") (class "Default")
      (node (ref "C16") (pin "1") (pinfunction "1_1") (pintype "passive"))
      (node (ref "U7") (pin "4") (pinfunction "BP_4") (pintype "input"))
    )
    (net (code "62") (name "Net-(U7-EN)") (class "Default")
      (node (ref "C14") (pin "1") (pinfunction "1_1") (pintype "passive"))
      (node (ref "L11") (pin "2") (pinfunction "2_2") (pintype "passive"))
      (node (ref "U7") (pin "1") (pinfunction "IN_1") (pintype "input"))
      (node (ref "U7") (pin "3") (pinfunction "EN_3") (pintype "input"))
    )
    (net (code "63") (name "Net-(U11-C1)") (class "Default")
      (node (ref "C23") (pin "1") (pinfunction "1_1") (pintype "passive"))
      (node (ref "U11") (pin "10") (pinfunction "C1_10") (pintype "bidirectional"))
    )
    (net (code "64") (name "Net-(U11-SETC)") (class "Default")
      (node (ref "C24") (pin "2") (pinfunction "2_2") (pintype "passive"))
      (node (ref "U11") (pin "12") (pinfunction "SETC_12") (pintype "bidirectional"))
    )
    (net (code "65") (name "Net-(U11-SETP)") (class "Default")
      (node (ref "C24") (pin "1") (pinfunction "1_1") (pintype "passive"))
      (node (ref "U11") (pin "8") (pinfunction "SETP_8") (pintype "bidirectional"))
    )
    (net (code "66") (name "Net-(U12-PLLFILT)") (class "Default")
      (node (ref "C25") (pin "1") (pinfunction "1_1") (pintype "passive"))
      (node (ref "U12") (pin "14") (pinfunction "PLLFILT_14") (pintype "bidirectional"))
    )
    (net (code "67") (name "Net-(U13-CLK)") (class "Default")
      (node (ref "RN1") (pin "8") (pinfunction "8_8") (pintype "passive"))
      (node (ref "U13") (pin "P$5") (pinfunction "CLK_P$5") (pintype "bidirectional"))
    )
    (net (code "68") (name "Net-(U13-CS)") (class "Default")
      (node (ref "RN1") (pin "5") (pinfunction "5_5") (pintype "passive"))
      (node (ref "U13") (pin "P$2") (pinfunction "CS_P$2") (pintype "bidirectional"))
    )
    (net (code "69") (name "Net-(U13-DI)") (class "Default")
      (node (ref "RN1") (pin "6") (pinfunction "6_6") (pintype "passive"))
      (node (ref "U13") (pin "P$3") (pinfunction "DI_P$3") (pintype "bidirectional"))
    )
    (net (code "70") (name "Net-(U13-DO)") (class "Default")
      (node (ref "RN1") (pin "7") (pinfunction "7_7") (pintype "passive"))
      (node (ref "U13") (pin "P$7") (pinfunction "DO_P$7") (pintype "bidirectional"))
    )
    (net (code "71") (name "Net-(U14-CPOUT)") (class "Default")
      (node (ref "C20") (pin "1") (pinfunction "1_1") (pintype "passive"))
      (node (ref "U14") (pin "20") (pinfunction "CPOUT_20") (pintype "bidirectional"))
    )
    (net (code "72") (name "Net-(U14-INT)") (class "Default")
      (node (ref "JP6") (pin "2") (pinfunction "2_2") (pintype "passive"))
      (node (ref "U14") (pin "12") (pinfunction "INT_12") (pintype "bidirectional"))
    )
    (net (code "73") (name "Net-(U14-REGOUT)") (class "Default")
      (node (ref "C26") (pin "1") (pinfunction "1_1") (pintype "passive"))
      (node (ref "U14") (pin "10") (pinfunction "REGOUT_10") (pintype "bidirectional"))
    )
    (net (code "74") (name "OTG_FS_DM") (class "Default")
      (node (ref "R6") (pin "2") (pinfunction "2_2") (pintype "passive"))
      (node (ref "U1") (pin "44") (pinfunction "PA11_44") (pintype "bidirectional"))
    )
    (net (code "75") (name "OTG_FS_DP") (class "Default")
      (node (ref "R8") (pin "2") (pinfunction "2_2") (pintype "passive"))
      (node (ref "U1") (pin "45") (pinfunction "PA12_45") (pintype "bidirectional"))
    )
    (net (code "76") (name "PB2-BOOT1") (class "Default")
      (node (ref "R5") (pin "1") (pinfunction "1_1") (pintype "passive"))
      (node (ref "U1") (pin "28") (pinfunction "PB2_28") (pintype "bidirectional"))
    )
    (net (code "77") (name "PPM_INPUT") (class "Default")
      (node (ref "J2") (pin "23") (pinfunction "S_23") (pintype "passive"))
      (node (ref "J3") (pin "23") (pinfunction "S_23") (pintype "passive"))
      (node (ref "R10") (pin "1") (pinfunction "1_1") (pintype "passive"))
      (node (ref "U1") (pin "43") (pinfunction "PA10_43") (pintype "bidirectional"))
    )
    (net (code "78") (name "RESET") (class "Default")
      (node (ref "!RESET") (pin "P$1") (pinfunction "P$1_P$1") (pintype "passive"))
      (node (ref "C17") (pin "2") (pinfunction "2_2") (pintype "passive"))
      (node (ref "R16") (pin "1") (pinfunction "1_1") (pintype "passive"))
      (node (ref "S1") (pin "A1") (pinfunction "1_A1") (pintype "passive"))
      (node (ref "U1") (pin "7") (pinfunction "NRST_7") (pintype "input"))
    )
    (net (code "79") (name "SPI1_MISO") (class "Default")
      (node (ref "SPI1_MISO") (pin "P$1") (pinfunction "P$1_P$1") (pintype "passive"))
      (node (ref "U1") (pin "22") (pinfunction "PA6_22") (pintype "bidirectional"))
      (node (ref "U12") (pin "4") (pinfunction "SDO/SA0_4") (pintype "bidirectional"))
      (node (ref "U14") (pin "9") (pinfunction "AD0/SDO_9") (pintype "bidirectional"))
      (node (ref "U15") (pin "1") (pinfunction "SDO_1") (pintype "bidirectional"))
    )
    (net (code "80") (name "SPI1_MOSI") (class "Default")
      (node (ref "SPI1_MOSI") (pin "P$1") (pinfunction "P$1_P$1") (pintype "passive"))
      (node (ref "U1") (pin "23") (pinfunction "PA7_23") (pintype "bidirectional"))
      (node (ref "U12") (pin "3") (pinfunction "SDA/SDI/SDO_3") (pintype "bidirectional"))
      (node (ref "U14") (pin "24") (pinfunction "SDA/SDI_24") (pintype "bidirectional"))
      (node (ref "U15") (pin "2") (pinfunction "SDI/SDA_2") (pintype "bidirectional"))
    )
    (net (code "81") (name "SPI1_SCK") (class "Default")
      (node (ref "SPI1_SCK") (pin "P$1") (pinfunction "P$1_P$1") (pintype "passive"))
      (node (ref "U1") (pin "21") (pinfunction "PA5_21") (pintype "bidirectional"))
      (node (ref "U12") (pin "2") (pinfunction "SCL/SPC_2") (pintype "input"))
      (node (ref "U14") (pin "23") (pinfunction "SCL/SCLK_23") (pintype "bidirectional"))
      (node (ref "U15") (pin "12") (pinfunction "SCK/SCL_12") (pintype "bidirectional"))
    )
    (net (code "82") (name "SPI3_MISO") (class "Default")
      (node (ref "R23") (pin "1") (pinfunction "1_1") (pintype "passive"))
      (node (ref "RN1") (pin "2") (pinfunction "2_2") (pintype "passive"))
      (node (ref "U1") (pin "52") (pinfunction "PC11_52") (pintype "bidirectional"))
    )
    (net (code "83") (name "SPI3_MOSI") (class "Default")
      (node (ref "RN1") (pin "3") (pinfunction "3_3") (pintype "passive"))
      (node (ref "U1") (pin "57") (pinfunction "PB5_57") (pintype "bidirectional"))
    )
    (net (code "84") (name "SPI3_NSS") (class "Default")
      (node (ref "RN1") (pin "4") (pinfunction "4_4") (pintype "passive"))
      (node (ref "U1") (pin "20") (pinfunction "PA4_20") (pintype "bidirectional"))
    )
    (net (code "85") (name "SPI3_SCK") (class "Default")
      (node (ref "RN1") (pin "1") (pinfunction "1_1") (pintype "passive"))
      (node (ref "U1") (pin "51") (pinfunction "PC10_51") (pintype "bidirectional"))
    )
    (net (code "86") (name "UART5_RX") (class "Default")
      (node (ref "J2") (pin "16") (pinfunction "S_16") (pintype "passive"))
      (node (ref "J3") (pin "16") (pinfunction "S_16") (pintype "passive"))
      (node (ref "U1") (pin "54") (pinfunction "PD2_54") (pintype "bidirectional"))
    )
    (net (code "87") (name "UART5_TX") (class "Default")
      (node (ref "J2") (pin "15") (pinfunction "S_15") (pintype "passive"))
      (node (ref "J3") (pin "15") (pinfunction "S_15") (pintype "passive"))
      (node (ref "U1") (pin "53") (pinfunction "PC12_53") (pintype "bidirectional"))
    )
    (net (code "88") (name "USART1_RX") (class "Default")
      (node (ref "U1") (pin "59") (pinfunction "PB7_59") (pintype "bidirectional"))
      (node (ref "U4") (pin "4") (pinfunction "A2_4") (pintype "bidirectional"))
    )
    (net (code "89") (name "USART1_RX_EXT") (class "Default")
      (node (ref "J1") (pin "7") (pinfunction "S_7") (pintype "passive"))
      (node (ref "J2") (pin "8") (pinfunction "S_8") (pintype "passive"))
      (node (ref "J3") (pin "8") (pinfunction "S_8") (pintype "passive"))
      (node (ref "U4") (pin "1") (pinfunction "B2_1") (pintype "bidirectional"))
    )
    (net (code "90") (name "USART1_TX") (class "Default")
      (node (ref "U1") (pin "58") (pinfunction "PB6_58") (pintype "bidirectional"))
      (node (ref "U4") (pin "5") (pinfunction "A1_5") (pintype "bidirectional"))
    )
    (net (code "91") (name "USART1_TX_EXT") (class "Default")
      (node (ref "J1") (pin "8") (pinfunction "S_8") (pintype "passive"))
      (node (ref "J2") (pin "7") (pinfunction "S_7") (pintype "passive"))
      (node (ref "J3") (pin "7") (pinfunction "S_7") (pintype "passive"))
      (node (ref "U4") (pin "8") (pinfunction "B1_8") (pintype "bidirectional"))
    )
    (net (code "92") (name "USART2_CTS") (class "Default")
      (node (ref "J2") (pin "19") (pinfunction "S_19") (pintype "passive"))
      (node (ref "J3") (pin "19") (pinfunction "S_19") (pintype "passive"))
      (node (ref "U1") (pin "14") (pinfunction "PA0_14") (pintype "bidirectional"))
      (node (ref "U2") (pin "5") (pinfunction "A1_5") (pintype "bidirectional"))
    )
    (net (code "93") (name "USART2_RTS") (class "Default")
      (node (ref "J2") (pin "20") (pinfunction "S_20") (pintype "passive"))
      (node (ref "J3") (pin "20") (pinfunction "S_20") (pintype "passive"))
      (node (ref "U1") (pin "15") (pinfunction "PA1_15") (pintype "bidirectional"))
      (node (ref "U2") (pin "4") (pinfunction "A2_4") (pintype "bidirectional"))
    )
    (net (code "94") (name "USART2_RX") (class "Default")
      (node (ref "J2") (pin "22") (pinfunction "S_22") (pintype "passive"))
      (node (ref "J3") (pin "22") (pinfunction "S_22") (pintype "passive"))
      (node (ref "U1") (pin "17") (pinfunction "PA3_17") (pintype "bidirectional"))
      (node (ref "U3") (pin "4") (pinfunction "A2_4") (pintype "bidirectional"))
    )
    (net (code "95") (name "USART2_TX") (class "Default")
      (node (ref "J2") (pin "21") (pinfunction "S_21") (pintype "passive"))
      (node (ref "J3") (pin "21") (pinfunction "S_21") (pintype "passive"))
      (node (ref "U1") (pin "16") (pinfunction "PA2_16") (pintype "bidirectional"))
      (node (ref "U3") (pin "5") (pinfunction "A1_5") (pintype "bidirectional"))
    )
    (net (code "96") (name "USART6_RX") (class "Default")
      (node (ref "J2") (pin "14") (pinfunction "S_14") (pintype "passive"))
      (node (ref "J3") (pin "14") (pinfunction "S_14") (pintype "passive"))
      (node (ref "L4") (pin "1") (pinfunction "1_1") (pintype "passive"))
      (node (ref "U1") (pin "38") (pinfunction "PC7_38") (pintype "bidirectional"))
      (node (ref "USART6_RX") (pin "P$1") (pinfunction "P$1_P$1") (pintype "passive"))
    )
    (net (code "97") (name "USART6_TX") (class "Default")
      (node (ref "J2") (pin "13") (pinfunction "S_13") (pintype "passive"))
      (node (ref "J3") (pin "13") (pinfunction "S_13") (pintype "passive"))
      (node (ref "L5") (pin "1") (pinfunction "1_1") (pintype "passive"))
      (node (ref "U1") (pin "37") (pinfunction "PC6_37") (pintype "bidirectional"))
      (node (ref "USART6_TX") (pin "P$1") (pinfunction "P$1_P$1") (pintype "passive"))
    )
    (net (code "98") (name "VBAT_IN") (class "Default")
      (node (ref "D2") (pin "1") (pinfunction "A1_1") (pintype "passive"))
      (node (ref "J1") (pin "5") (pinfunction "S_5") (pintype "passive"))
      (node (ref "L10") (pin "2") (pinfunction "2_2") (pintype "passive"))
    )
    (net (code "99") (name "VBUS") (class "Default")
      (node (ref "J5") (pin "VBUS") (pinfunction "1_VBUS") (pintype "power_in"))
      (node (ref "L8") (pin "2") (pinfunction "2_2") (pintype "passive"))
      (node (ref "U1") (pin "42") (pinfunction "PA9_42") (pintype "bidirectional"))
    )
    (net (code "100") (name "VDD_3V3") (class "Default")
      (node (ref "C10") (pin "1") (pinfunction "1_1") (pintype "passive"))
      (node (ref "C2") (pin "1") (pinfunction "1_1") (pintype "passive"))
      (node (ref "C6") (pin "A") (pinfunction "+_A") (pintype "passive"))
      (node (ref "C8") (pin "1") (pinfunction "1_1") (pintype "passive"))
      (node (ref "C9") (pin "1") (pinfunction "1_1") (pintype "passive"))
      (node (ref "F1") (pin "1") (pinfunction "1_1") (pintype "bidirectional"))
      (node (ref "J6") (pin "1") (pinfunction "S_1") (pintype "passive"))
      (node (ref "JP1") (pin "1") (pinfunction "1_1") (pintype "passive"))
      (node (ref "JP2") (pin "3") (pinfunction "3_3") (pintype "passive"))
      (node (ref "LED1") (pin "A") (pinfunction "A_A") (pintype "passive"))
      (node (ref "LED2") (pin "A") (pinfunction "A_A") (pintype "passive"))
      (node (ref "LED3") (pin "A") (pinfunction "A_A") (pintype "passive"))
      (node (ref "R16") (pin "2") (pinfunction "2_2") (pintype "passive"))
      (node (ref "R19") (pin "2") (pinfunction "2_2") (pintype "passive"))
      (node (ref "R20") (pin "2") (pinfunction "2_2") (pintype "passive"))
      (node (ref "R23") (pin "2") (pinfunction "2_2") (pintype "passive"))
      (node (ref "R7") (pin "2") (pinfunction "2_2") (pintype "passive"))
      (node (ref "R9") (pin "2") (pinfunction "2_2") (pintype "passive"))
      (node (ref "U1") (pin "1") (pinfunction "VBAT_1") (pintype "power_in"))
      (node (ref "U1") (pin "19") (pinfunction "VDD_4_19") (pintype "power_in"))
      (node (ref "U1") (pin "32") (pinfunction "VDD_1_32") (pintype "power_in"))
      (node (ref "U1") (pin "48") (pinfunction "VDD_2_48") (pintype "power_in"))
      (node (ref "U1") (pin "64") (pinfunction "VDD_3_64") (pintype "power_in"))
      (node (ref "U12") (pin "1") (pinfunction "VDD_IO_1") (pintype "bidirectional"))
      (node (ref "U13") (pin "P$4") (pinfunction "VCC_P$4") (pintype "passive"))
      (node (ref "U15") (pin "3") (pinfunction "VDDIO_3") (pintype "bidirectional"))
      (node (ref "U2") (pin "3") (pinfunction "VCCA_3") (pintype "input"))
      (node (ref "U2") (pin "6") (pinfunction "OE_6") (pintype "input"))
      (node (ref "U3") (pin "3") (pinfunction "VCCA_3") (pintype "input"))
      (node (ref "U3") (pin "6") (pinfunction "OE_6") (pintype "input"))
      (node (ref "U4") (pin "3") (pinfunction "VCCA_3") (pintype "input"))
      (node (ref "U4") (pin "6") (pinfunction "OE_6") (pintype "input"))
      (node (ref "U4") (pin "7") (pinfunction "VCCB_7") (pintype "input"))
      (node (ref "U5") (pin "1") (pinfunction "VCCA_1") (pintype "passive"))
      (node (ref "U6") (pin "2") (pinfunction "VOUT_2") (pintype "bidirectional"))
      (node (ref "U6") (pin "4") (pinfunction "VOUT-TAB_4") (pintype "bidirectional"))
      (node (ref "U8") (pin "8") (pinfunction "VCC_8") (pintype "power_in"))
      (node (ref "VDD_3V3") (pin "P$1") (pinfunction "P$1_P$1") (pintype "passive"))
    )
    (net (code "101") (name "VDD_3V3_ANALOG") (class "Default")
      (node (ref "C13") (pin "A") (pinfunction "+_A") (pintype "passive"))
      (node (ref "C15") (pin "1") (pinfunction "1_1") (pintype "passive"))
      (node (ref "C18") (pin "1") (pinfunction "1_1") (pintype "passive"))
      (node (ref "C19") (pin "1") (pinfunction "1_1") (pintype "passive"))
      (node (ref "C21") (pin "1") (pinfunction "1_1") (pintype "passive"))
      (node (ref "C22") (pin "1") (pinfunction "1_1") (pintype "passive"))
      (node (ref "C28") (pin "1") (pinfunction "1_1") (pintype "passive"))
      (node (ref "U1") (pin "13") (pinfunction "VDDA_13") (pintype "power_in"))
      (node (ref "U10") (pin "1") (pinfunction "VDD_1") (pintype "bidirectional"))
      (node (ref "U10") (pin "2") (pinfunction "PS_2") (pintype "bidirectional"))
      (node (ref "U10") (pin "4") (pinfunction "CSB1_4") (pintype "bidirectional"))
      (node (ref "U10") (pin "5") (pinfunction "CSB2_5") (pintype "bidirectional"))
      (node (ref "U11") (pin "13") (pinfunction "VDDIO_13") (pintype "bidirectional"))
      (node (ref "U11") (pin "2") (pinfunction "VDD_2") (pintype "bidirectional"))
      (node (ref "U11") (pin "4") (pinfunction "S1_VDDIO_4") (pintype "bidirectional"))
      (node (ref "U12") (pin "15") (pinfunction "RES_P15_VDD_15") (pintype "bidirectional"))
      (node (ref "U12") (pin "16") (pinfunction "VDD_16") (pintype "bidirectional"))
      (node (ref "U14") (pin "13") (pinfunction "VDD_13") (pintype "bidirectional"))
      (node (ref "U15") (pin "7") (pinfunction "VDD_7") (pintype "bidirectional"))
      (node (ref "U7") (pin "5") (pinfunction "OUT_5") (pintype "passive"))
      (node (ref "VDDA_3V3") (pin "P$1") (pinfunction "P$1_P$1") (pintype "passive"))
    )
    (net (code "102") (name "VDD_5V") (class "Default")
      (node (ref "C27") (pin "A") (pinfunction "+_A") (pintype "passive"))
      (node (ref "C7") (pin "1") (pinfunction "1_1") (pintype "passive"))
      (node (ref "D2") (pin "2") (pinfunction "A2_2") (pintype "passive"))
      (node (ref "JP1") (pin "3") (pinfunction "3_3") (pintype "passive"))
      (node (ref "JP2") (pin "1") (pinfunction "1_1") (pintype "passive"))
      (node (ref "L1") (pin "1") (pinfunction "1_1") (pintype "passive"))
      (node (ref "L11") (pin "1") (pinfunction "1_1") (pintype "passive"))
      (node (ref "Q1") (pin "4") (pinfunction "S_4") (pintype "passive"))
      (node (ref "R1") (pin "2") (pinfunction "2_2") (pintype "passive"))
      (node (ref "R2") (pin "2") (pinfunction "2_2") (pintype "passive"))
      (node (ref "U6") (pin "3") (pinfunction "VIN_3") (pintype "bidirectional"))
    )
    (net (code "103") (name "VDD_5V_IN") (class "Default")
      (node (ref "D1") (pin "CATHODE") (pinfunction "C_CATHODE") (pintype "passive"))
      (node (ref "J2") (pin "1") (pinfunction "S_1") (pintype "passive"))
      (node (ref "J2") (pin "2") (pinfunction "S_2") (pintype "passive"))
      (node (ref "J3") (pin "1") (pinfunction "S_1") (pintype "passive"))
      (node (ref "J3") (pin "2") (pinfunction "S_2") (pintype "passive"))
      (node (ref "Q1") (pin "1") (pinfunction "D_1") (pintype "passive"))
      (node (ref "Q1") (pin "2") (pinfunction "D1_2") (pintype "passive"))
      (node (ref "Q1") (pin "5") (pinfunction "D2_5") (pintype "passive"))
      (node (ref "Q1") (pin "6") (pinfunction "D3_6") (pintype "passive"))
    )
    (net (code "104") (name "VDD_IO") (class "Default")
      (node (ref "C1") (pin "1") (pinfunction "1_1") (pintype "passive"))
      (node (ref "JP1") (pin "2") (pinfunction "2_2") (pintype "passive"))
      (node (ref "U2") (pin "7") (pinfunction "VCCB_7") (pintype "input"))
      (node (ref "U3") (pin "7") (pinfunction "VCCB_7") (pintype "input"))
      (node (ref "U5") (pin "8") (pinfunction "VCCB_8") (pintype "passive"))
    )
    (net (code "105") (name "unconnected-(J4D-S-Pad4)") (class "Default")
      (node (ref "J4") (pin "4") (pinfunction "S_4") (pintype "passive"))
    )
    (net (code "106") (name "unconnected-(J5-4-PadID)") (class "Default")
      (node (ref "J5") (pin "ID") (pinfunction "4_ID") (pintype "passive"))
    )
    (net (code "107") (name "unconnected-(U8-WP-Pad7)") (class "Default")
      (node (ref "U8") (pin "7") (pinfunction "WP_7") (pintype "bidirectional"))
    )
    (net (code "108") (name "unconnected-(U10-SDO-Pad6)") (class "Default")
      (node (ref "U10") (pin "6") (pinfunction "SDO_6") (pintype "bidirectional"))
    )
    (net (code "109") (name "unconnected-(U11-NC_P3-Pad3)") (class "Default")
      (node (ref "U11") (pin "3") (pinfunction "NC_P3_3") (pintype "no_connect"))
    )
    (net (code "110") (name "unconnected-(U11-NC_P5-Pad5)") (class "Default")
      (node (ref "U11") (pin "5") (pinfunction "NC_P5_5") (pintype "no_connect"))
    )
    (net (code "111") (name "unconnected-(U11-NC_P6-Pad6)") (class "Default")
      (node (ref "U11") (pin "6") (pinfunction "NC_P6_6") (pintype "no_connect"))
    )
    (net (code "112") (name "unconnected-(U11-NC_P7-Pad7)") (class "Default")
      (node (ref "U11") (pin "7") (pinfunction "NC_P7_7") (pintype "no_connect"))
    )
    (net (code "113") (name "unconnected-(U11-NC_P14-Pad14)") (class "Default")
      (node (ref "U11") (pin "14") (pinfunction "NC_P14_14") (pintype "no_connect"))
    )
    (net (code "114") (name "unconnected-(U12-DRDY{slash}INT2-Pad6)") (class "Default")
      (node (ref "U12") (pin "6") (pinfunction "DRDY/INT2_6") (pintype "output"))
    )
    (net (code "115") (name "unconnected-(U12-INT1-Pad7)") (class "Default")
      (node (ref "U12") (pin "7") (pinfunction "INT1_7") (pintype "output"))
    )
    (net (code "116") (name "unconnected-(U14-AUX_CL-Pad7)") (class "Default")
      (node (ref "U14") (pin "7") (pinfunction "AUX_CL_7") (pintype "bidirectional"))
    )
    (net (code "117") (name "unconnected-(U14-AUX_DA-Pad6)") (class "Default")
      (node (ref "U14") (pin "6") (pinfunction "AUX_DA_6") (pintype "bidirectional"))
    )
    (net (code "118") (name "unconnected-(U14-CLKOUT-Pad22)") (class "Default")
      (node (ref "U14") (pin "22") (pinfunction "CLKOUT_22") (pintype "bidirectional"))
    )
    (net (code "119") (name "unconnected-(U14-NC1-Pad2)") (class "Default")
      (node (ref "U14") (pin "2") (pinfunction "NC1_2") (pintype "bidirectional"))
    )
    (net (code "120") (name "unconnected-(U14-NC2-Pad3)") (class "Default")
      (node (ref "U14") (pin "3") (pinfunction "NC2_3") (pintype "bidirectional"))
    )
    (net (code "121") (name "unconnected-(U14-NC3-Pad4)") (class "Default")
      (node (ref "U14") (pin "4") (pinfunction "NC3_4") (pintype "bidirectional"))
    )
    (net (code "122") (name "unconnected-(U14-NC4-Pad5)") (class "Default")
      (node (ref "U14") (pin "5") (pinfunction "NC4_5") (pintype "bidirectional"))
    )
    (net (code "123") (name "unconnected-(U14-NC5-Pad14)") (class "Default")
      (node (ref "U14") (pin "14") (pinfunction "NC5_14") (pintype "bidirectional"))
    )
    (net (code "124") (name "unconnected-(U14-NC6-Pad15)") (class "Default")
      (node (ref "U14") (pin "15") (pinfunction "NC6_15") (pintype "bidirectional"))
    )
    (net (code "125") (name "unconnected-(U14-NC7-Pad16)") (class "Default")
      (node (ref "U14") (pin "16") (pinfunction "NC7_16") (pintype "bidirectional"))
    )
    (net (code "126") (name "unconnected-(U14-NC8-Pad17)") (class "Default")
      (node (ref "U14") (pin "17") (pinfunction "NC8_17") (pintype "bidirectional"))
    )
    (net (code "127") (name "unconnected-(U14-RESV1-Pad19)") (class "Default")
      (node (ref "U14") (pin "19") (pinfunction "RESV1_19") (pintype "bidirectional"))
    )
    (net (code "128") (name "unconnected-(U14-RESV2-Pad21)") (class "Default")
      (node (ref "U14") (pin "21") (pinfunction "RESV2_21") (pintype "bidirectional"))
    )
    (net (code "129") (name "unconnected-(U15-INT1-Pad5)") (class "Default")
      (node (ref "U15") (pin "5") (pinfunction "INT1_5") (pintype "bidirectional"))
    )
    (net (code "130") (name "unconnected-(U15-INT2-Pad6)") (class "Default")
      (node (ref "U15") (pin "6") (pinfunction "INT2_6") (pintype "bidirectional"))
    )
    (net (code "131") (name "~{JTRST}") (class "Default")
      (node (ref "!JTRST") (pin "P$1") (pinfunction "P$1_P$1") (pintype "passive"))
      (node (ref "J6") (pin "10") (pinfunction "S_10") (pintype "passive"))
      (node (ref "U1") (pin "56") (pinfunction "PB4_56") (pintype "bidirectional"))
    )
  )
)
